# MSP-EXP432P401R.net
KiCad netlist of a schematic drawn in EAGLE
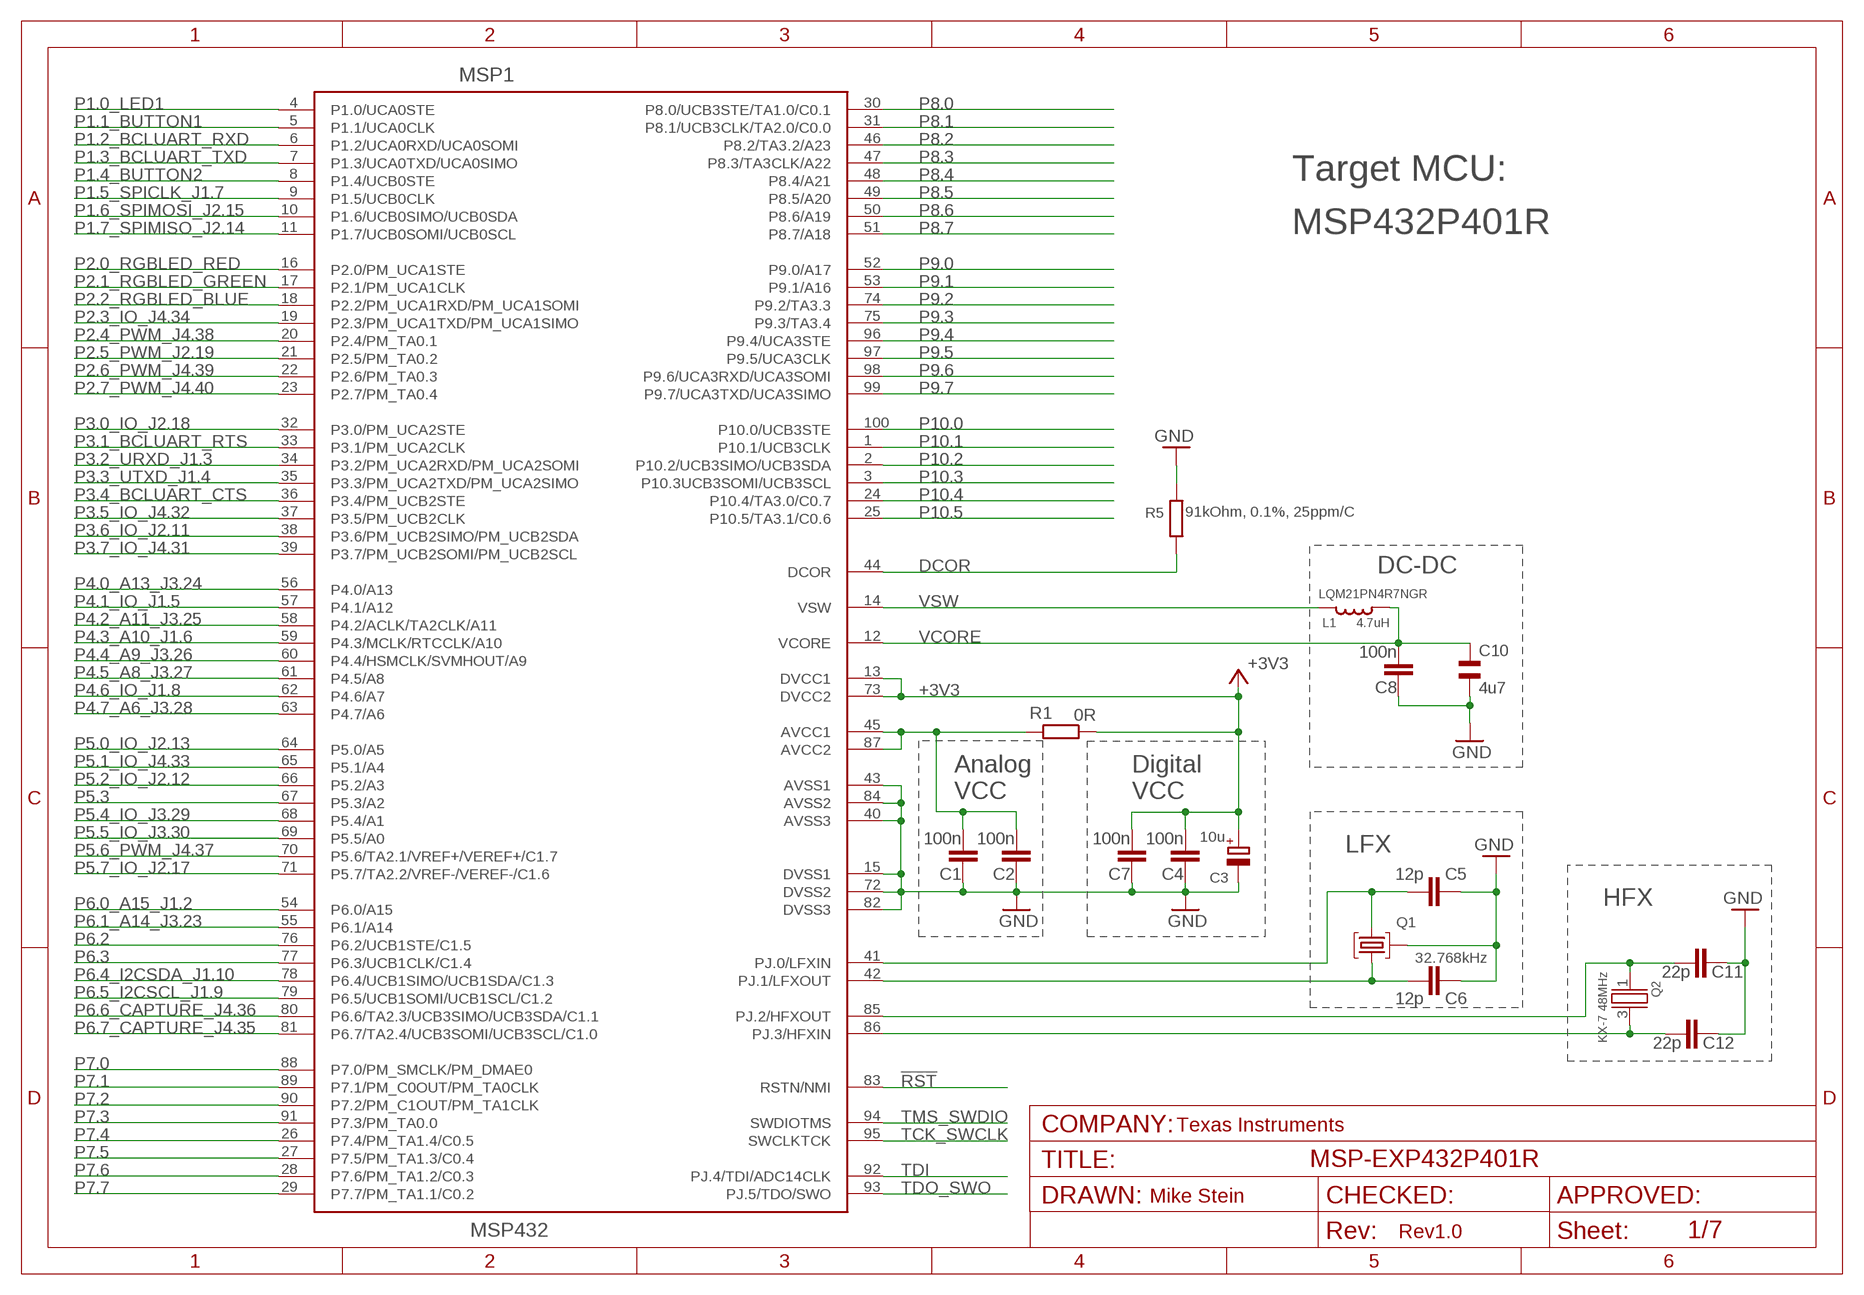
[diagram p0: schematic, sheet 1]
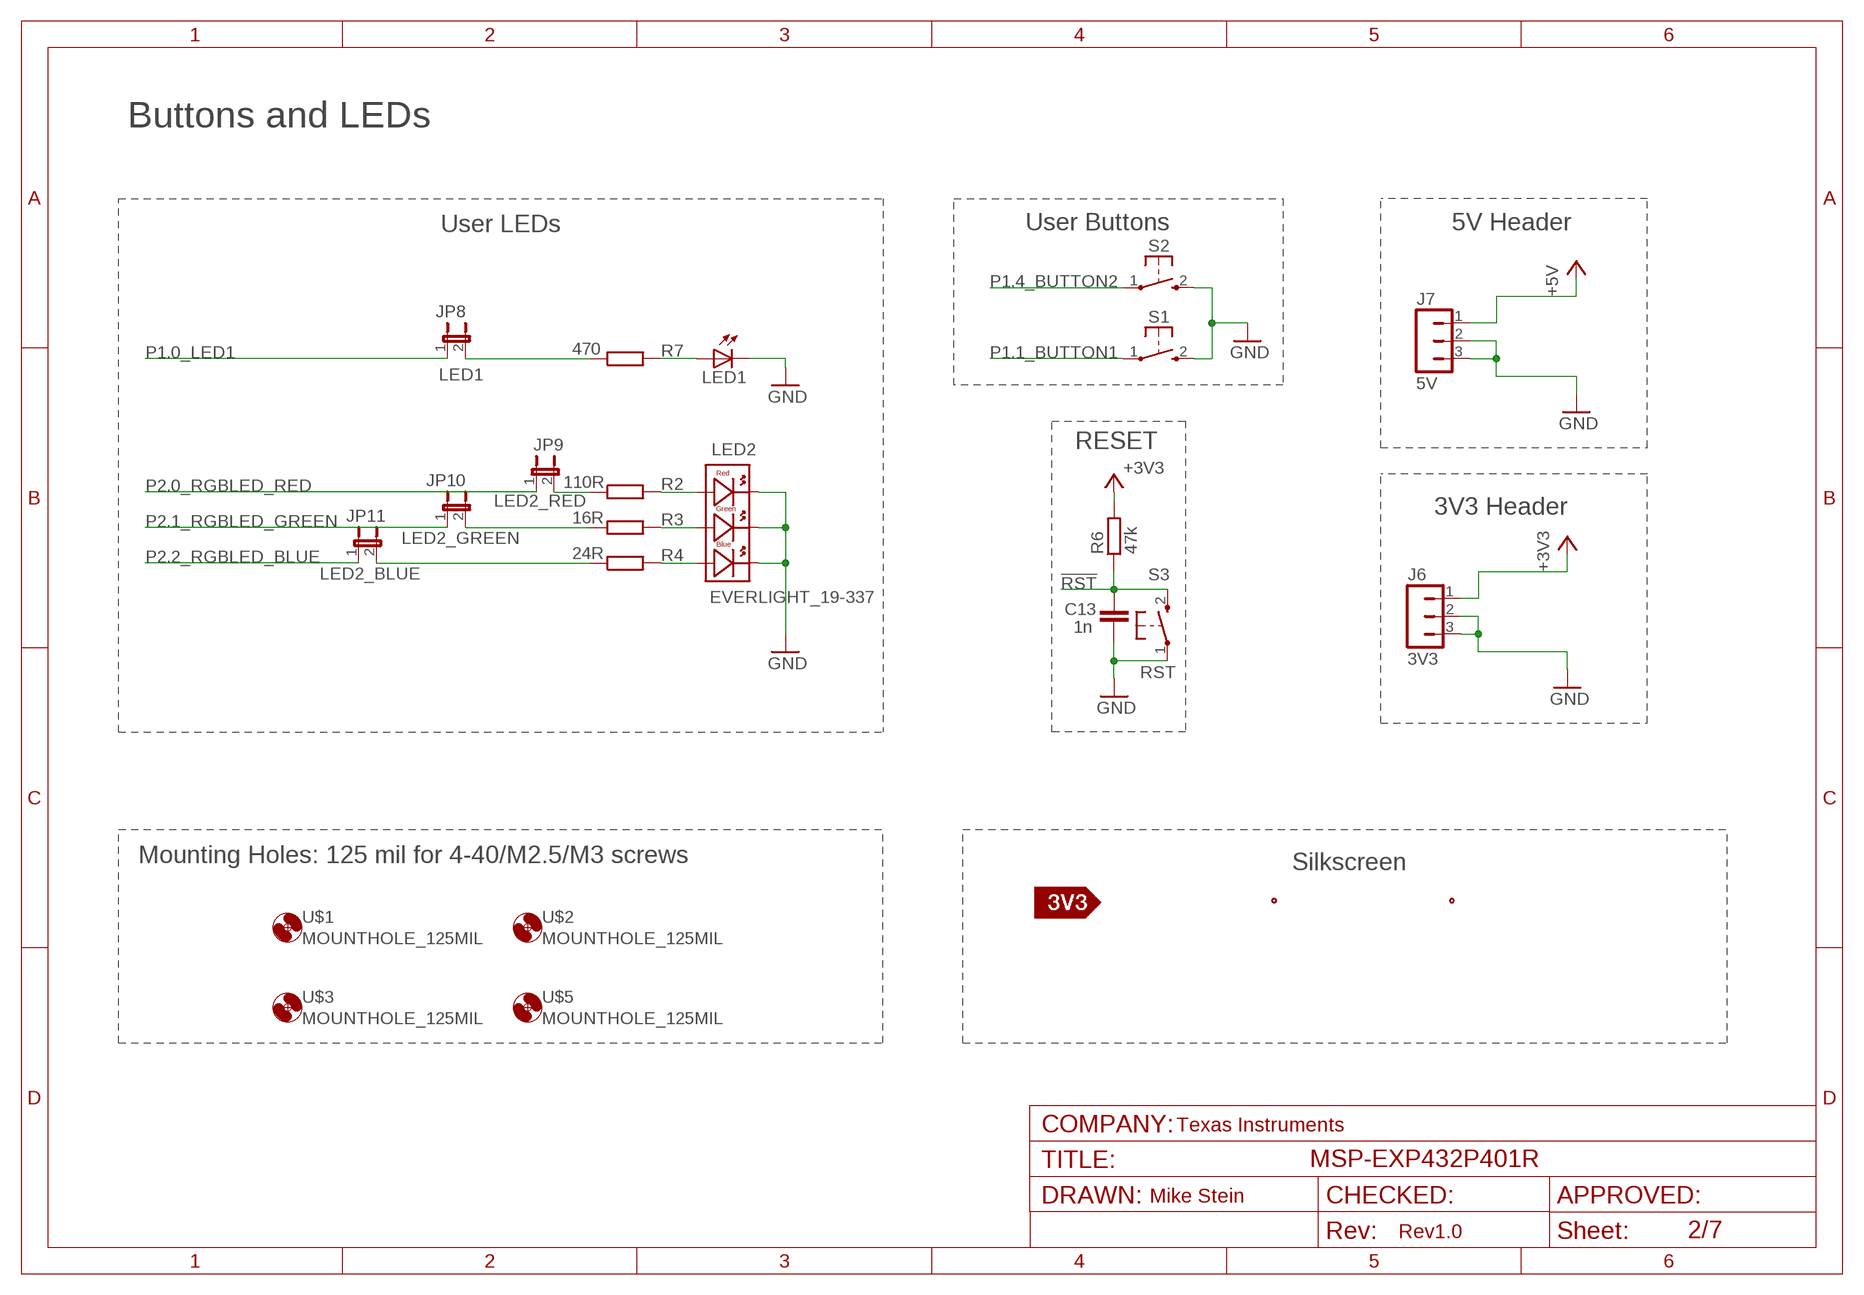
[diagram p1: schematic, sheet 2]
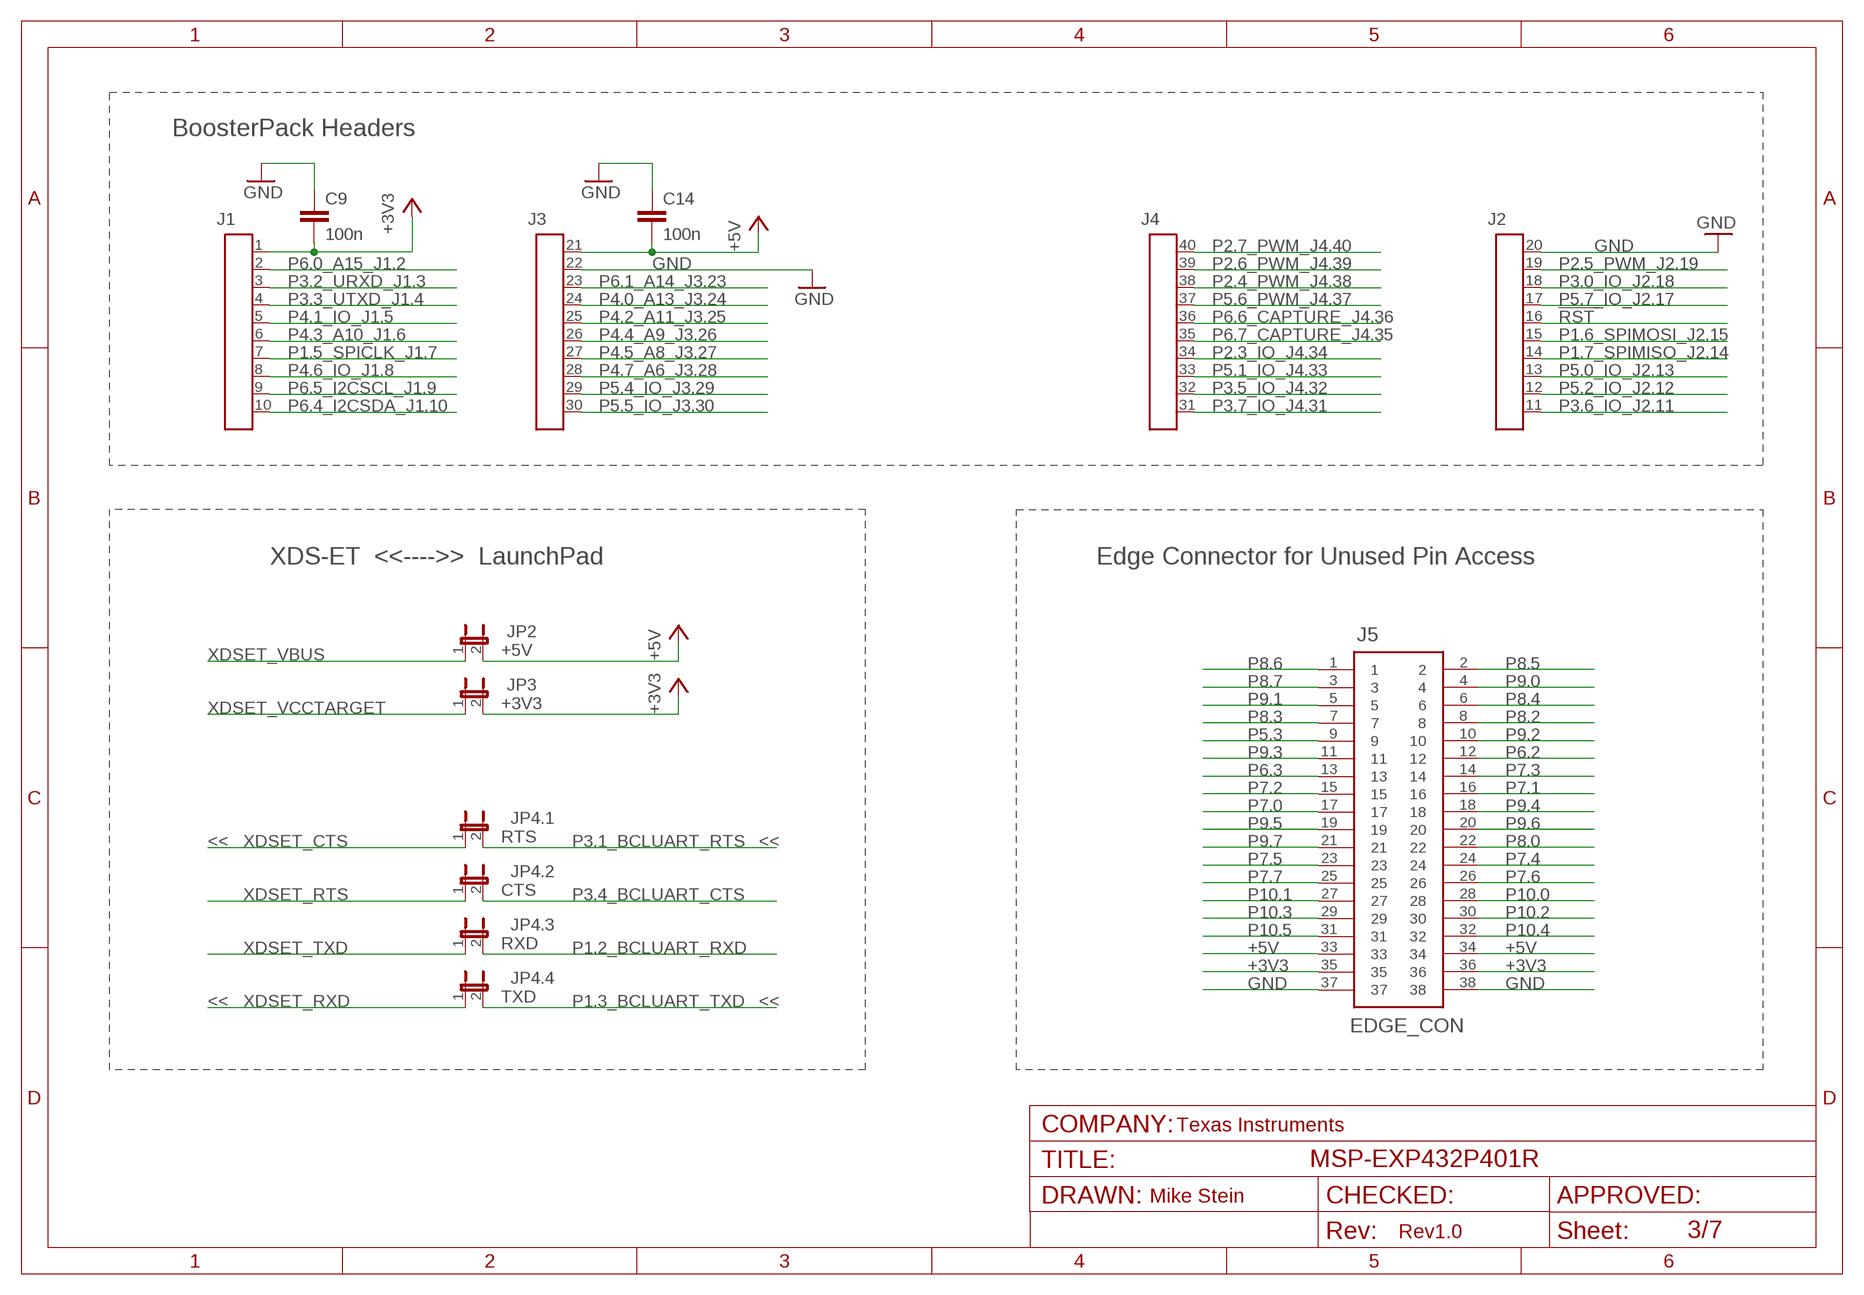
[diagram p2: schematic, sheet 3]
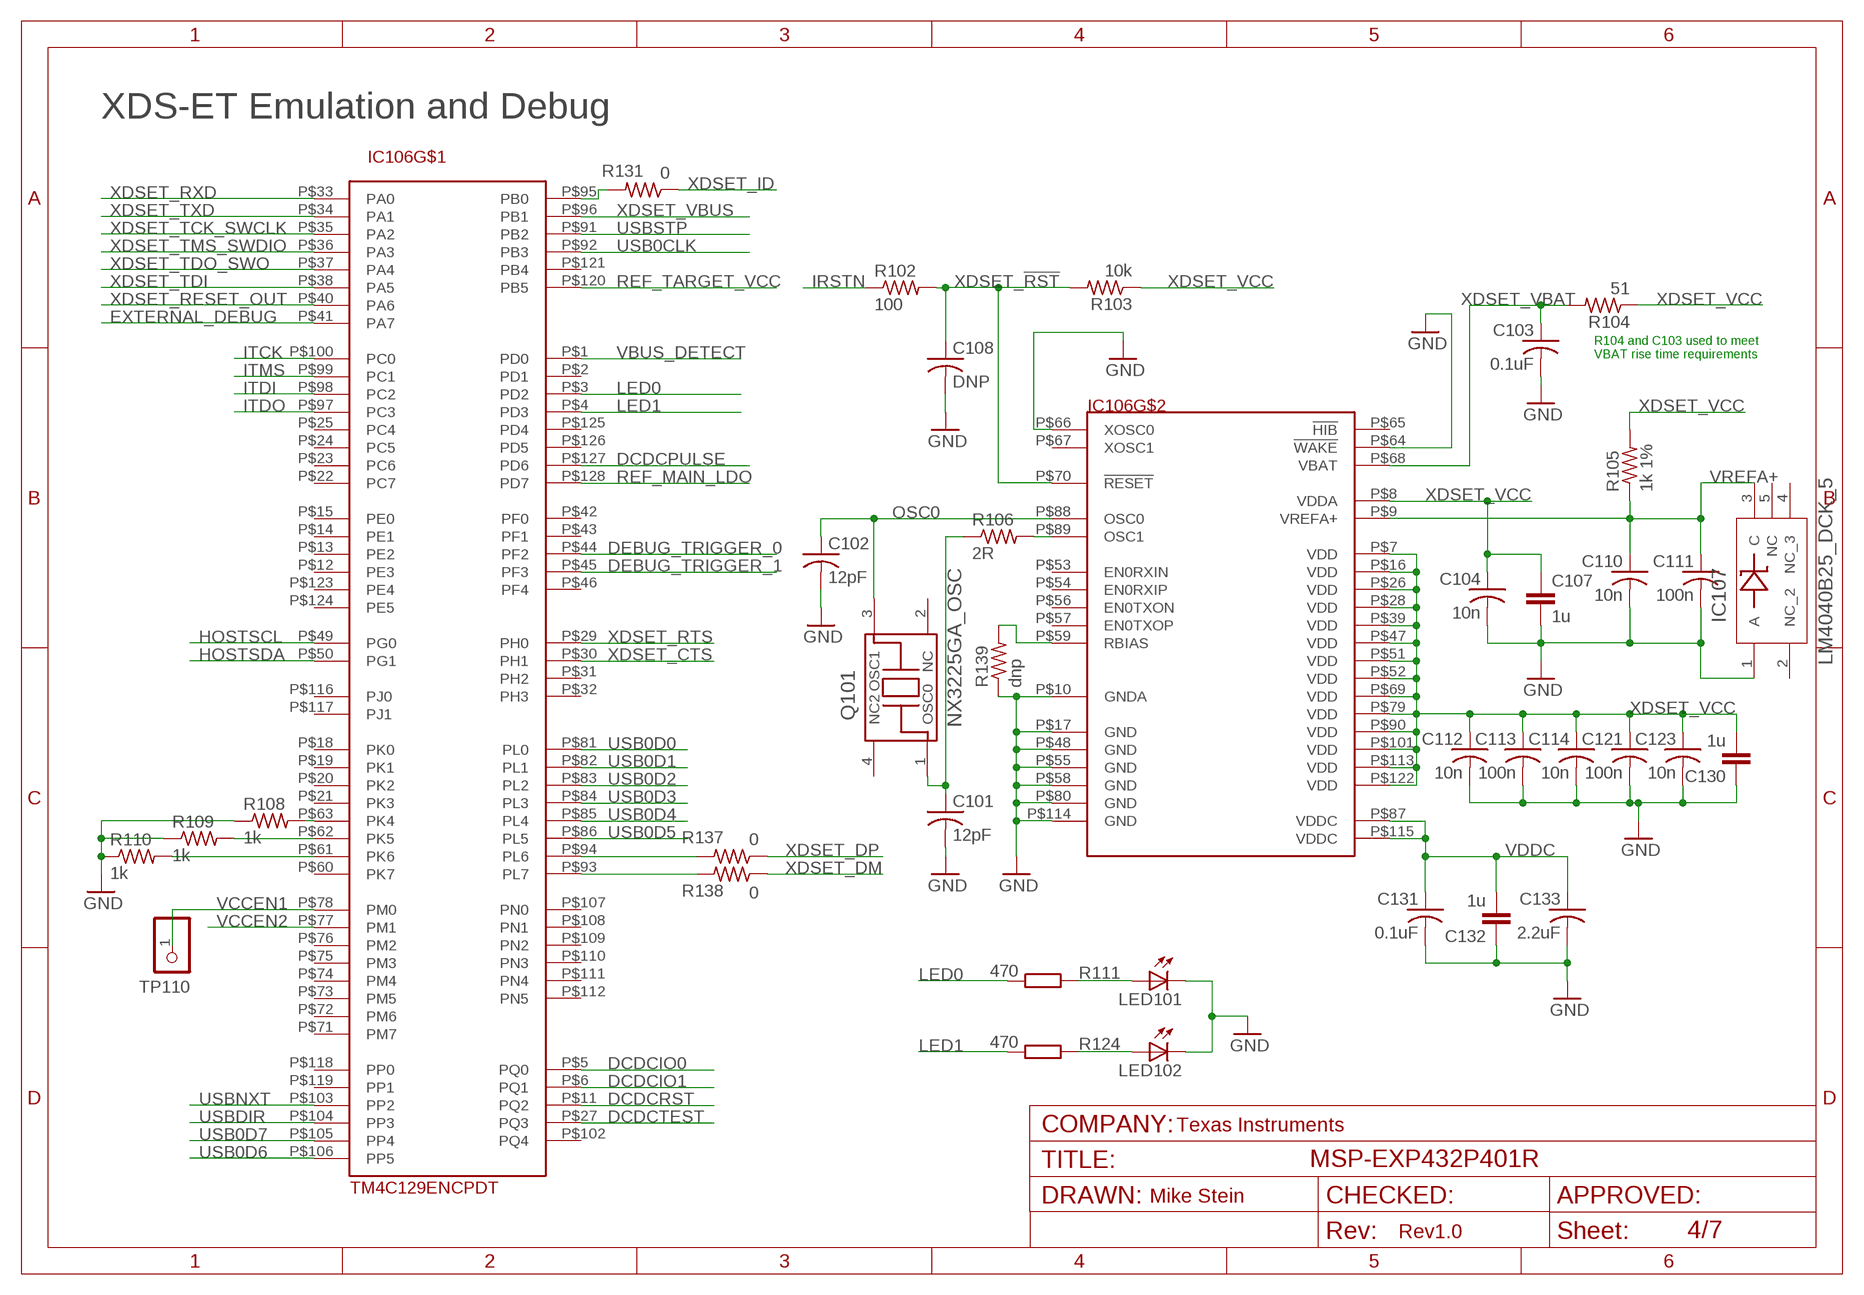
[diagram p3: schematic, sheet 4]
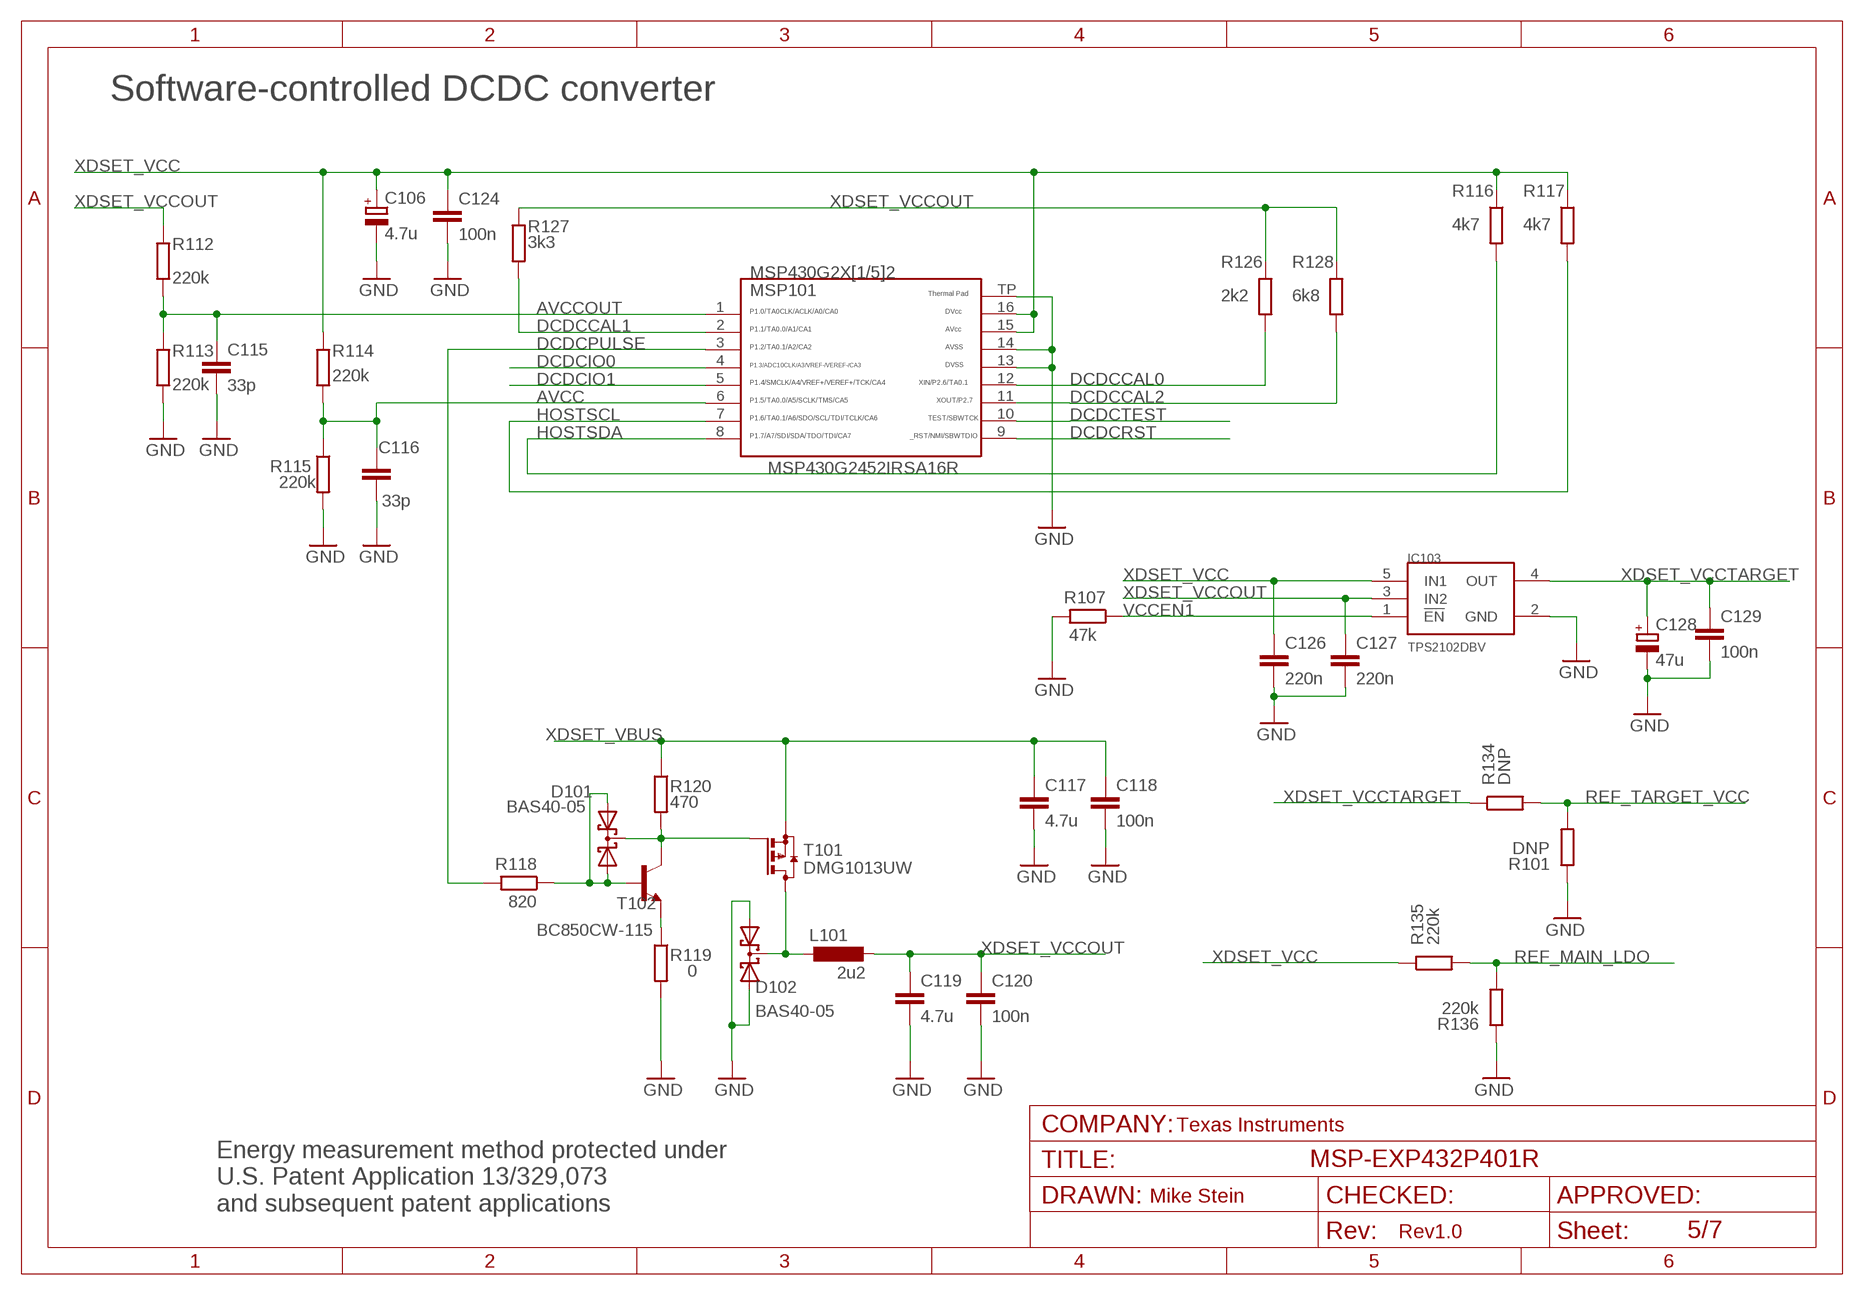
[diagram p4: schematic, sheet 5]
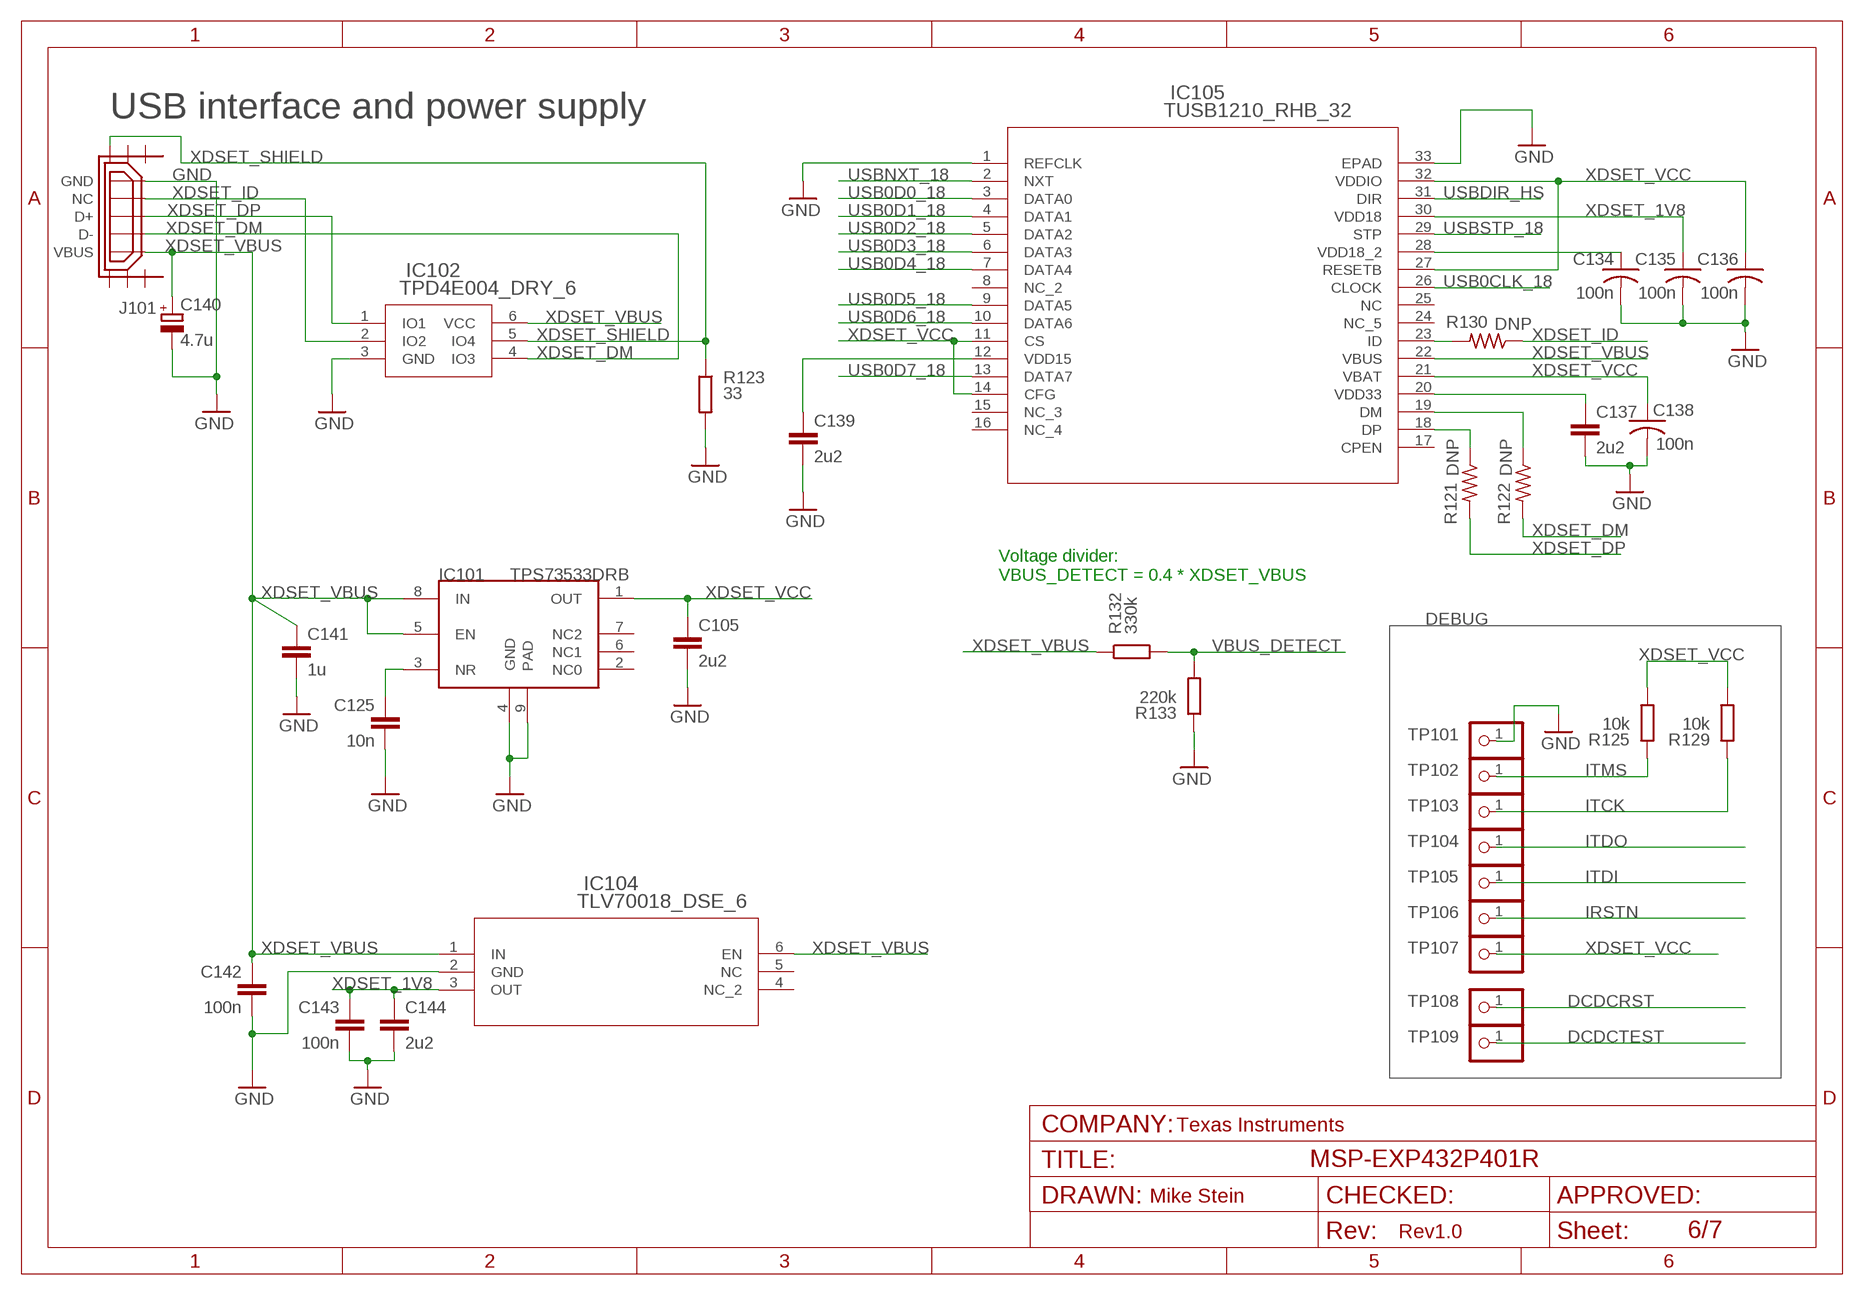
[diagram p5: schematic, sheet 6]
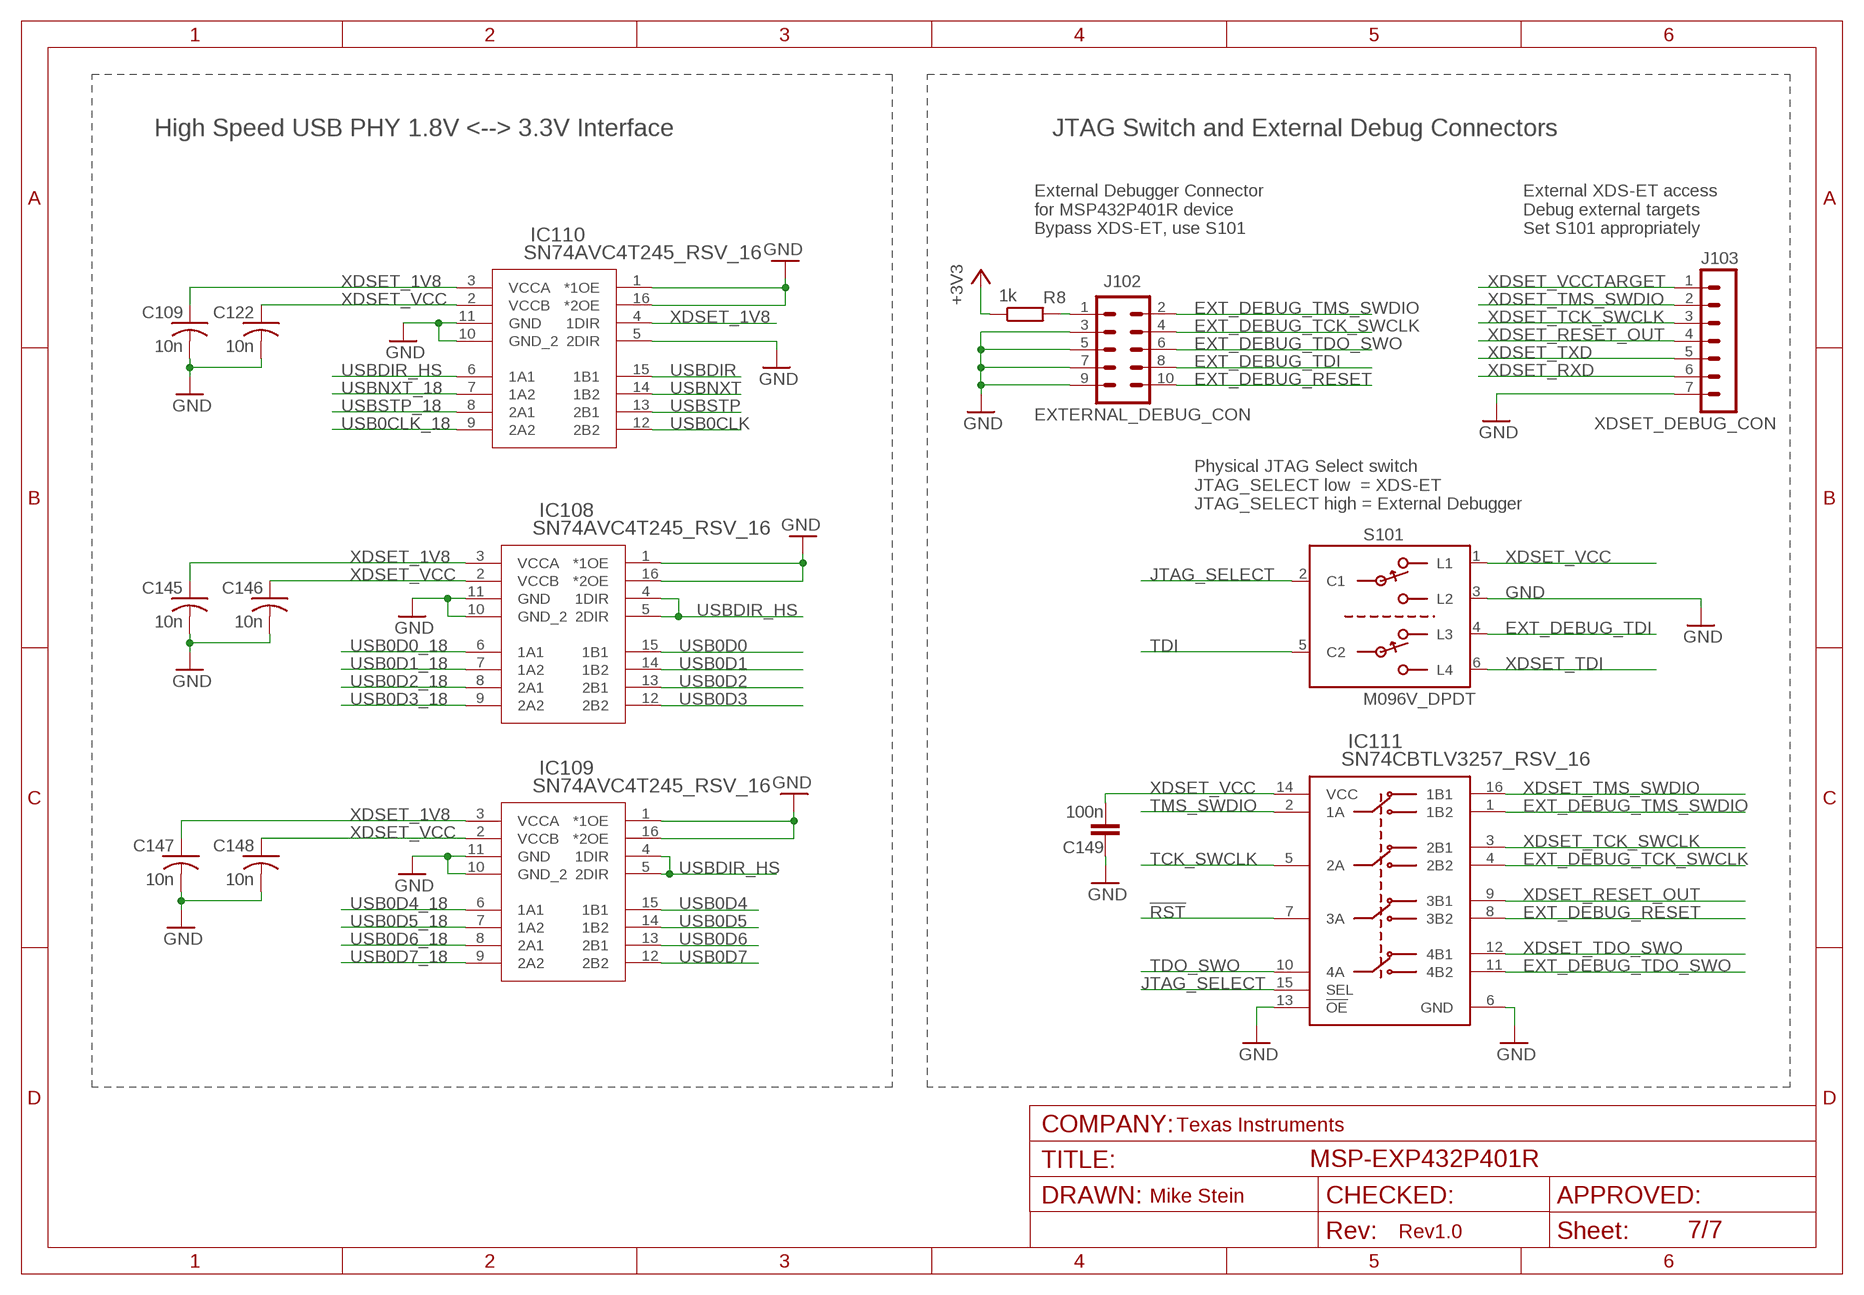
[diagram p6: schematic, sheet 7]

(export (version "E")
  (design (tool "Eeschema 10.0.6"))
  (components
    (comp (ref "C105")
      (value "2u2")
      (footprint "eagle-import:C0603")
      (libsource (lib "eagle-import") (part "C-EUC0603"))
    )
    (comp (ref "C125")
      (value "10n")
      (footprint "eagle-import:0402")
      (libsource (lib "eagle-import") (part "C-EUCM0402"))
    )
    (comp (ref "C134")
      (value "100n")
      (footprint "eagle-import:C0402")
      (libsource (lib "eagle-import") (part "C-USC0402"))
    )
    (comp (ref "C135")
      (value "100n")
      (footprint "eagle-import:C0402")
      (libsource (lib "eagle-import") (part "C-USC0402"))
    )
    (comp (ref "C136")
      (value "100n")
      (footprint "eagle-import:C0402")
      (libsource (lib "eagle-import") (part "C-USC0402"))
    )
    (comp (ref "C137")
      (value "2u2")
      (footprint "eagle-import:C0603")
      (libsource (lib "eagle-import") (part "C-EUC0603"))
    )
    (comp (ref "C138")
      (value "100n")
      (footprint "eagle-import:C0402")
      (libsource (lib "eagle-import") (part "C-USC0402"))
    )
    (comp (ref "C139")
      (value "2u2")
      (footprint "eagle-import:C0603")
      (libsource (lib "eagle-import") (part "C-EUC0603"))
    )
    (comp (ref "C140")
      (value "4.7u")
      (footprint "eagle-import:A_3216-18R")
      (libsource (lib "eagle-import") (part "CPOL-EUA/3216-18R"))
    )
    (comp (ref "C141")
      (value "1u")
      (footprint "eagle-import:C0603")
      (libsource (lib "eagle-import") (part "C-EUC0603"))
    )
    (comp (ref "C142")
      (value "100n")
      (footprint "eagle-import:0402")
      (libsource (lib "eagle-import") (part "C-EUCM0402"))
    )
    (comp (ref "C143")
      (value "100n")
      (footprint "eagle-import:0402")
      (libsource (lib "eagle-import") (part "C-EUCM0402"))
    )
    (comp (ref "C144")
      (value "2u2")
      (footprint "eagle-import:C0603")
      (libsource (lib "eagle-import") (part "C-EUC0603"))
    )
    (comp (ref "IC101")
      (value "TPS73533DRB")
      (footprint "eagle-import:SON8")
      (libsource (lib "eagle-import") (part "TPS73633DRB"))
    )
    (comp (ref "IC102")
      (value "TPD4E004_DRY_6")
      (footprint "eagle-import:DRY6")
      (fields
        (field (name "GENERIC_PART_NUMBER") "TPD4E004")
        (field (name "MANUFACTURER") "Texas Instruments")
        (field (name "MANUFACTURER_PART_NUMBER") "tpd4e004_dry_6")
      )
      (libsource (lib "eagle-import") (part "TPD4E004_DRY_6"))
    )
    (comp (ref "IC104")
      (value "TLV70018_DSE_6")
      (footprint "eagle-import:DSE6")
      (fields
        (field (name "GENERIC_PART_NUMBER") "TLV70018")
        (field (name "MANUFACTURER") "Texas Instruments")
        (field (name "MANUFACTURER_PART_NUMBER") "tlv70018_dse_6")
      )
      (libsource (lib "eagle-import") (part "TLV70018_DSE_6"))
    )
    (comp (ref "IC105")
      (value "TUSB1210_RHB_32")
      (footprint "eagle-import:RHB32_3P45X3P45")
      (fields
        (field (name "GENERIC_PART_NUMBER") "TUSB1210")
        (field (name "MANUFACTURER") "Texas Instruments")
        (field (name "MANUFACTURER_PART_NUMBER") "tusb1210_rhb_32")
      )
      (libsource (lib "eagle-import") (part "TUSB1210_RHB_32"))
    )
    (comp (ref "J101")
      (value "USB_MICRO_FLIPPED")
      (footprint "eagle-import:HIROSE-ZX62R-B-5P")
      (libsource (lib "eagle-import") (part "USB_MICRO_FLIPPED"))
    )
    (comp (ref "R121")
      (value "DNP")
      (footprint "eagle-import:R0402")
      (libsource (lib "eagle-import") (part "R-US_R0402"))
    )
    (comp (ref "R122")
      (value "DNP")
      (footprint "eagle-import:R0402")
      (libsource (lib "eagle-import") (part "R-US_R0402"))
    )
    (comp (ref "R123")
      (value "33")
      (footprint "eagle-import:0402")
      (libsource (lib "eagle-import") (part "R-EU_RM0402"))
    )
    (comp (ref "R125")
      (value "10k")
      (footprint "eagle-import:0402")
      (libsource (lib "eagle-import") (part "R-EU_RM0402"))
    )
    (comp (ref "R129")
      (value "10k")
      (footprint "eagle-import:0402")
      (libsource (lib "eagle-import") (part "R-EU_RM0402"))
    )
    (comp (ref "R130")
      (value "DNP")
      (footprint "eagle-import:R0402")
      (libsource (lib "eagle-import") (part "R-US_R0402"))
    )
    (comp (ref "R132")
      (value "330k")
      (footprint "eagle-import:0402")
      (libsource (lib "eagle-import") (part "R-EU_RM0402"))
    )
    (comp (ref "R133")
      (value "220k")
      (footprint "eagle-import:0402")
      (libsource (lib "eagle-import") (part "R-EU_RM0402"))
    )
    (comp (ref "TP101")
      (value "TEST_PIN2")
      (footprint "eagle-import:1X01")
      (libsource (lib "eagle-import") (part "PINHD-1X1"))
    )
    (comp (ref "TP102")
      (value "TEST_PIN2")
      (footprint "eagle-import:1X01")
      (libsource (lib "eagle-import") (part "PINHD-1X1"))
    )
    (comp (ref "TP103")
      (value "TEST_PIN2")
      (footprint "eagle-import:1X01")
      (libsource (lib "eagle-import") (part "PINHD-1X1"))
    )
    (comp (ref "TP104")
      (value "TEST_PIN2")
      (footprint "eagle-import:1X01")
      (libsource (lib "eagle-import") (part "PINHD-1X1"))
    )
    (comp (ref "TP105")
      (value "TEST_PIN2")
      (footprint "eagle-import:1X01")
      (libsource (lib "eagle-import") (part "PINHD-1X1"))
    )
    (comp (ref "TP106")
      (value "TEST_PIN2")
      (footprint "eagle-import:1X01")
      (libsource (lib "eagle-import") (part "PINHD-1X1"))
    )
    (comp (ref "TP107")
      (value "TEST_PIN2")
      (footprint "eagle-import:1X01")
      (libsource (lib "eagle-import") (part "PINHD-1X1"))
    )
    (comp (ref "TP108")
      (value "TEST_PIN2")
      (footprint "eagle-import:1X01")
      (libsource (lib "eagle-import") (part "PINHD-1X1"))
    )
    (comp (ref "TP109")
      (value "TEST_PIN2")
      (footprint "eagle-import:1X01")
      (libsource (lib "eagle-import") (part "PINHD-1X1"))
    )
    (comp (ref "C109")
      (value "10n")
      (footprint "eagle-import:C0402")
      (libsource (lib "eagle-import") (part "C-USC0402"))
    )
    (comp (ref "C122")
      (value "10n")
      (footprint "eagle-import:C0402")
      (libsource (lib "eagle-import") (part "C-USC0402"))
    )
    (comp (ref "C145")
      (value "10n")
      (footprint "eagle-import:C0402")
      (libsource (lib "eagle-import") (part "C-USC0402"))
    )
    (comp (ref "C146")
      (value "10n")
      (footprint "eagle-import:C0402")
      (libsource (lib "eagle-import") (part "C-USC0402"))
    )
    (comp (ref "C147")
      (value "10n")
      (footprint "eagle-import:C0402")
      (libsource (lib "eagle-import") (part "C-USC0402"))
    )
    (comp (ref "C148")
      (value "10n")
      (footprint "eagle-import:C0402")
      (libsource (lib "eagle-import") (part "C-USC0402"))
    )
    (comp (ref "C149")
      (value "100n")
      (footprint "eagle-import:0402")
      (libsource (lib "eagle-import") (part "C-EUCM0402"))
    )
    (comp (ref "IC108")
      (value "SN74AVC4T245_RSV_16")
      (footprint "eagle-import:RSV16")
      (fields
        (field (name "GENERIC_PART_NUMBER") "SN74AVC4T245")
        (field (name "MANUFACTURER") "Texas Instruments")
        (field (name "MANUFACTURER_PART_NUMBER") "sn74avc4t245_rsv_16")
      )
      (libsource (lib "eagle-import") (part "SN74AVC4T245_RSV_16"))
    )
    (comp (ref "IC109")
      (value "SN74AVC4T245_RSV_16")
      (footprint "eagle-import:RSV16")
      (fields
        (field (name "GENERIC_PART_NUMBER") "SN74AVC4T245")
        (field (name "MANUFACTURER") "Texas Instruments")
        (field (name "MANUFACTURER_PART_NUMBER") "sn74avc4t245_rsv_16")
      )
      (libsource (lib "eagle-import") (part "SN74AVC4T245_RSV_16"))
    )
    (comp (ref "IC110")
      (value "SN74AVC4T245_RSV_16")
      (footprint "eagle-import:RSV16")
      (fields
        (field (name "GENERIC_PART_NUMBER") "SN74AVC4T245")
        (field (name "MANUFACTURER") "Texas Instruments")
        (field (name "MANUFACTURER_PART_NUMBER") "sn74avc4t245_rsv_16")
      )
      (libsource (lib "eagle-import") (part "SN74AVC4T245_RSV_16"))
    )
    (comp (ref "IC111")
      (value "SN74CBTLV3257_RSV_16")
      (footprint "eagle-import:RSV16")
      (libsource (lib "eagle-import") (part "SN74CBTLV3257_RSV_16"))
    )
    (comp (ref "J102")
      (value "EXTERNAL_DEBUG_CON")
      (footprint "eagle-import:EXTERNAL_DEBUG")
      (libsource (lib "eagle-import") (part "EXTERNAL_DEBUG_CON"))
    )
    (comp (ref "J103")
      (value "XDSET_DEBUG_CON")
      (footprint "eagle-import:XDSET_DEBUG")
      (libsource (lib "eagle-import") (part "XDSET_DEBUG_CON"))
    )
    (comp (ref "R8")
      (value "1k")
      (footprint "eagle-import:0402")
      (libsource (lib "eagle-import") (part "R-EU_RM0402"))
    )
    (comp (ref "S101")
      (value "M096V_DPDT")
      (footprint "eagle-import:M096V_DPDT")
      (libsource (lib "eagle-import") (part "M096V_DPDT"))
    )
    (comp (ref "C101")
      (value "12pF")
      (footprint "eagle-import:C0402")
      (libsource (lib "eagle-import") (part "C-USC0402"))
    )
    (comp (ref "C102")
      (value "12pF")
      (footprint "eagle-import:C0402")
      (libsource (lib "eagle-import") (part "C-USC0402"))
    )
    (comp (ref "C103")
      (value "0.1uF")
      (footprint "eagle-import:C0402")
      (libsource (lib "eagle-import") (part "C-USC0402"))
    )
    (comp (ref "C104")
      (value "10n")
      (footprint "eagle-import:C0402")
      (libsource (lib "eagle-import") (part "C-USC0402"))
    )
    (comp (ref "C107")
      (value "1u")
      (footprint "eagle-import:C0603")
      (libsource (lib "eagle-import") (part "C-EUC0603"))
    )
    (comp (ref "C108")
      (value "DNP")
      (footprint "eagle-import:C0402")
      (libsource (lib "eagle-import") (part "C-USC0402"))
    )
    (comp (ref "C110")
      (value "10n")
      (footprint "eagle-import:C0402")
      (libsource (lib "eagle-import") (part "C-USC0402"))
    )
    (comp (ref "C111")
      (value "100n")
      (footprint "eagle-import:C0402")
      (libsource (lib "eagle-import") (part "C-USC0402"))
    )
    (comp (ref "C112")
      (value "10n")
      (footprint "eagle-import:C0402")
      (libsource (lib "eagle-import") (part "C-USC0402"))
    )
    (comp (ref "C113")
      (value "100n")
      (footprint "eagle-import:C0402")
      (libsource (lib "eagle-import") (part "C-USC0402"))
    )
    (comp (ref "C114")
      (value "10n")
      (footprint "eagle-import:C0402")
      (libsource (lib "eagle-import") (part "C-USC0402"))
    )
    (comp (ref "C121")
      (value "100n")
      (footprint "eagle-import:C0402")
      (libsource (lib "eagle-import") (part "C-USC0402"))
    )
    (comp (ref "C123")
      (value "10n")
      (footprint "eagle-import:C0402")
      (libsource (lib "eagle-import") (part "C-USC0402"))
    )
    (comp (ref "C130")
      (value "1u")
      (footprint "eagle-import:C0603")
      (libsource (lib "eagle-import") (part "C-EUC0603"))
    )
    (comp (ref "C131")
      (value "0.1uF")
      (footprint "eagle-import:C0402")
      (libsource (lib "eagle-import") (part "C-USC0402"))
    )
    (comp (ref "C132")
      (value "1u")
      (footprint "eagle-import:C0603")
      (libsource (lib "eagle-import") (part "C-EUC0603"))
    )
    (comp (ref "C133")
      (value "2.2uF")
      (footprint "eagle-import:C0603K")
      (fields (field (name "DIGIKEY_PARTNUM") "311-1451-2-ND"))
      (libsource (lib "eagle-import") (part "C-USC0603K"))
    )
    (comp (ref "IC106")
      (value "TM4C129ENCPDT")
      (footprint "eagle-import:TQFP-128")
      (libsource (lib "eagle-import") (part "TM4C129ENCPDT"))
    )
    (comp (ref "IC107")
      (value "LM4040B25_DCK_5")
      (footprint "eagle-import:DCK5")
      (fields
        (field (name "GENERIC_PART_NUMBER") "LM4040B25")
        (field (name "MANUFACTURER") "Texas Instruments")
        (field (name "MANUFACTURER_PART_NUMBER") "lm4040b25_dck_5")
      )
      (libsource (lib "eagle-import") (part "LM4040B25_DCK_5"))
    )
    (comp (ref "LED101")
      (value "LEDCHIPLED_0603")
      (footprint "eagle-import:CHIPLED_0603")
      (libsource (lib "eagle-import") (part "LEDCHIPLED_0603"))
    )
    (comp (ref "LED102")
      (value "LEDCHIPLED_0603")
      (footprint "eagle-import:CHIPLED_0603")
      (libsource (lib "eagle-import") (part "LEDCHIPLED_0603"))
    )
    (comp (ref "Q101")
      (value "NX3225GA_OSC")
      (footprint "eagle-import:NX3225GA")
      (libsource (lib "eagle-import") (part "NX3225GA_OSC"))
    )
    (comp (ref "R102")
      (value "100")
      (footprint "eagle-import:R0402")
      (libsource (lib "eagle-import") (part "R-US_R0402"))
    )
    (comp (ref "R103")
      (value "10k")
      (footprint "eagle-import:R0402")
      (libsource (lib "eagle-import") (part "R-US_R0402"))
    )
    (comp (ref "R104")
      (value "51")
      (footprint "eagle-import:R0402")
      (libsource (lib "eagle-import") (part "R-US_R0402"))
    )
    (comp (ref "R105")
      (value "1k 1%")
      (footprint "eagle-import:R0402")
      (libsource (lib "eagle-import") (part "R-US_R0402"))
    )
    (comp (ref "R106")
      (value "2R")
      (footprint "eagle-import:R0402")
      (libsource (lib "eagle-import") (part "R-US_R0402"))
    )
    (comp (ref "R108")
      (value "1k")
      (footprint "eagle-import:R0402")
      (libsource (lib "eagle-import") (part "R-US_R0402"))
    )
    (comp (ref "R109")
      (value "1k")
      (footprint "eagle-import:R0402")
      (libsource (lib "eagle-import") (part "R-US_R0402"))
    )
    (comp (ref "R110")
      (value "1k")
      (footprint "eagle-import:R0402")
      (libsource (lib "eagle-import") (part "R-US_R0402"))
    )
    (comp (ref "R111")
      (value "470")
      (footprint "eagle-import:0402")
      (libsource (lib "eagle-import") (part "R-EU_RM0402"))
    )
    (comp (ref "R124")
      (value "470")
      (footprint "eagle-import:0402")
      (libsource (lib "eagle-import") (part "R-EU_RM0402"))
    )
    (comp (ref "R131")
      (value "0")
      (footprint "eagle-import:R0402")
      (libsource (lib "eagle-import") (part "R-US_R0402"))
    )
    (comp (ref "R137")
      (value "0")
      (footprint "eagle-import:R0402")
      (libsource (lib "eagle-import") (part "R-US_R0402"))
    )
    (comp (ref "R138")
      (value "0")
      (footprint "eagle-import:R0402")
      (libsource (lib "eagle-import") (part "R-US_R0402"))
    )
    (comp (ref "R139")
      (value "dnp")
      (footprint "eagle-import:R0402")
      (libsource (lib "eagle-import") (part "R-US_R0402"))
    )
    (comp (ref "TP110")
      (value "TEST_PIN2")
      (footprint "eagle-import:1X01")
      (libsource (lib "eagle-import") (part "PINHD-1X1"))
    )
    (comp (ref "C106")
      (value "4.7u")
      (footprint "eagle-import:A_3216-18R")
      (libsource (lib "eagle-import") (part "CPOL-EUA/3216-18R"))
    )
    (comp (ref "C115")
      (value "33p")
      (footprint "eagle-import:0402")
      (libsource (lib "eagle-import") (part "C-EUCM0402"))
    )
    (comp (ref "C116")
      (value "33p")
      (footprint "eagle-import:0402")
      (libsource (lib "eagle-import") (part "C-EUCM0402"))
    )
    (comp (ref "C117")
      (value "4.7u")
      (footprint "eagle-import:C0603")
      (libsource (lib "eagle-import") (part "C-EUC0603"))
    )
    (comp (ref "C118")
      (value "100n")
      (footprint "eagle-import:0402")
      (libsource (lib "eagle-import") (part "C-EUCM0402"))
    )
    (comp (ref "C119")
      (value "4.7u")
      (footprint "eagle-import:C0603")
      (libsource (lib "eagle-import") (part "C-EUC0603"))
    )
    (comp (ref "C120")
      (value "100n")
      (footprint "eagle-import:0402")
      (libsource (lib "eagle-import") (part "C-EUCM0402"))
    )
    (comp (ref "C124")
      (value "100n")
      (footprint "eagle-import:0402")
      (libsource (lib "eagle-import") (part "C-EUCM0402"))
    )
    (comp (ref "C126")
      (value "220n")
      (footprint "eagle-import:0402")
      (libsource (lib "eagle-import") (part "C-EUCM0402"))
    )
    (comp (ref "C127")
      (value "220n")
      (footprint "eagle-import:0402")
      (libsource (lib "eagle-import") (part "C-EUCM0402"))
    )
    (comp (ref "C128")
      (value "47u")
      (footprint "eagle-import:A_3216-18R")
      (libsource (lib "eagle-import") (part "CPOL-EUA/3216-18R"))
    )
    (comp (ref "C129")
      (value "100n")
      (footprint "eagle-import:0402")
      (libsource (lib "eagle-import") (part "C-EUCM0402"))
    )
    (comp (ref "D101")
      (value "BAS40-05")
      (footprint "eagle-import:SOT23")
      (libsource (lib "eagle-import") (part "BAS70-05"))
    )
    (comp (ref "D102")
      (value "BAS40-05")
      (footprint "eagle-import:SOT23")
      (libsource (lib "eagle-import") (part "BAS70-05"))
    )
    (comp (ref "IC103")
      (value "TPS2102DBV")
      (footprint "eagle-import:SOT23-5")
      (libsource (lib "eagle-import") (part "TPS2102DBV"))
    )
    (comp (ref "L101")
      (value "2u2")
      (footprint "eagle-import:L3216C")
      (libsource (lib "eagle-import") (part "L-EUL3216C"))
    )
    (comp (ref "MSP101")
      (value "MSP430G2452IRSA16R")
      (footprint "eagle-import:RSA16")
      (libsource (lib "eagle-import") (part "G2X[1/5]2---RSA16"))
    )
    (comp (ref "R101")
      (value "DNP")
      (footprint "eagle-import:0402")
      (libsource (lib "eagle-import") (part "R-EU_RM0402"))
    )
    (comp (ref "R107")
      (value "47k")
      (footprint "eagle-import:0402")
      (libsource (lib "eagle-import") (part "R-EU_RM0402"))
    )
    (comp (ref "R112")
      (value "220k")
      (footprint "eagle-import:0402")
      (libsource (lib "eagle-import") (part "R-EU_RM0402"))
    )
    (comp (ref "R113")
      (value "220k")
      (footprint "eagle-import:0402")
      (libsource (lib "eagle-import") (part "R-EU_RM0402"))
    )
    (comp (ref "R114")
      (value "220k")
      (footprint "eagle-import:0402")
      (libsource (lib "eagle-import") (part "R-EU_RM0402"))
    )
    (comp (ref "R115")
      (value "220k")
      (footprint "eagle-import:0402")
      (libsource (lib "eagle-import") (part "R-EU_RM0402"))
    )
    (comp (ref "R116")
      (value "4k7")
      (footprint "eagle-import:0402")
      (libsource (lib "eagle-import") (part "R-EU_RM0402"))
    )
    (comp (ref "R117")
      (value "4k7")
      (footprint "eagle-import:0402")
      (libsource (lib "eagle-import") (part "R-EU_RM0402"))
    )
    (comp (ref "R118")
      (value "820")
      (footprint "eagle-import:0402")
      (libsource (lib "eagle-import") (part "R-EU_RM0402"))
    )
    (comp (ref "R119")
      (value "0")
      (footprint "eagle-import:0402")
      (libsource (lib "eagle-import") (part "R-EU_RM0402"))
    )
    (comp (ref "R120")
      (value "470")
      (footprint "eagle-import:0402")
      (libsource (lib "eagle-import") (part "R-EU_RM0402"))
    )
    (comp (ref "R126")
      (value "2k2")
      (footprint "eagle-import:0402")
      (libsource (lib "eagle-import") (part "R-EU_RM0402"))
    )
    (comp (ref "R127")
      (value "3k3")
      (footprint "eagle-import:0402")
      (libsource (lib "eagle-import") (part "R-EU_RM0402"))
    )
    (comp (ref "R128")
      (value "6k8")
      (footprint "eagle-import:0402")
      (libsource (lib "eagle-import") (part "R-EU_RM0402"))
    )
    (comp (ref "R134")
      (value "DNP")
      (footprint "eagle-import:0402")
      (libsource (lib "eagle-import") (part "R-EU_RM0402"))
    )
    (comp (ref "R135")
      (value "220k")
      (footprint "eagle-import:0402")
      (libsource (lib "eagle-import") (part "R-EU_RM0402"))
    )
    (comp (ref "R136")
      (value "220k")
      (footprint "eagle-import:0402")
      (libsource (lib "eagle-import") (part "R-EU_RM0402"))
    )
    (comp (ref "T101")
      (value "DMG1013UW")
      (footprint "eagle-import:SOT23")
      (libsource (lib "eagle-import") (part "BSS84"))
    )
    (comp (ref "T102")
      (value "BC850CW-115")
      (footprint "eagle-import:SOT23-BEC")
      (libsource (lib "eagle-import") (part "BC850SMD"))
    )
    (comp (ref "C9")
      (value "100n")
      (footprint "eagle-import:0402")
      (libsource (lib "eagle-import") (part "C-EUCM0402"))
    )
    (comp (ref "C14")
      (value "100n")
      (footprint "eagle-import:0402")
      (libsource (lib "eagle-import") (part "C-EUCM0402"))
    )
    (comp (ref "J1")
      (value "HEADER1X10")
      (footprint "eagle-import:1X10")
      (libsource (lib "eagle-import") (part "HEADER1X10"))
    )
    (comp (ref "J2")
      (value "HEADER1X10-J2")
      (footprint "eagle-import:1X10-J2")
      (libsource (lib "eagle-import") (part "HEADER1X10-J2"))
    )
    (comp (ref "J3")
      (value "HEADER1X10-J3")
      (footprint "eagle-import:1X10-J3")
      (libsource (lib "eagle-import") (part "HEADER1X10-J3"))
    )
    (comp (ref "J4")
      (value "HEADER1X10-J4")
      (footprint "eagle-import:1X10-J4")
      (libsource (lib "eagle-import") (part "HEADER1X10-J4"))
    )
    (comp (ref "J5")
      (value "EDGE_CON")
      (footprint "eagle-import:BOTTOM_CONNECTOR")
      (libsource (lib "eagle-import") (part "EDGE_CON"))
    )
    (comp (ref "JP2")
      (value "+5V")
      (footprint "eagle-import:JP1M")
      (libsource (lib "eagle-import") (part "JP1M"))
    )
    (comp (ref "JP3")
      (value "+3V3")
      (footprint "eagle-import:JP1M")
      (libsource (lib "eagle-import") (part "JP1M"))
    )
    (comp (ref "JP4.1")
      (value "RTS")
      (footprint "eagle-import:JP1M")
      (libsource (lib "eagle-import") (part "JP1M"))
    )
    (comp (ref "JP4.2")
      (value "CTS")
      (footprint "eagle-import:JP1M")
      (libsource (lib "eagle-import") (part "JP1M"))
    )
    (comp (ref "JP4.3")
      (value "RXD")
      (footprint "eagle-import:JP1M")
      (libsource (lib "eagle-import") (part "JP1M"))
    )
    (comp (ref "JP4.4")
      (value "TXD")
      (footprint "eagle-import:JP1M")
      (libsource (lib "eagle-import") (part "JP1M"))
    )
    (comp (ref "C1")
      (value "100n")
      (footprint "eagle-import:0402")
      (libsource (lib "eagle-import") (part "C-EUCM0402"))
    )
    (comp (ref "C2")
      (value "100n")
      (footprint "eagle-import:0402")
      (libsource (lib "eagle-import") (part "C-EUCM0402"))
    )
    (comp (ref "C3")
      (value "10u")
      (footprint "eagle-import:A_3216-18R")
      (libsource (lib "eagle-import") (part "CPOL-EUA/3216-18R"))
    )
    (comp (ref "C4")
      (value "100n")
      (footprint "eagle-import:0402")
      (libsource (lib "eagle-import") (part "C-EUCM0402"))
    )
    (comp (ref "C5")
      (value "12p")
      (footprint "eagle-import:0402")
      (libsource (lib "eagle-import") (part "C-EUCM0402"))
    )
    (comp (ref "C6")
      (value "12p")
      (footprint "eagle-import:0402")
      (libsource (lib "eagle-import") (part "C-EUCM0402"))
    )
    (comp (ref "C7")
      (value "100n")
      (footprint "eagle-import:0402")
      (libsource (lib "eagle-import") (part "C-EUCM0402"))
    )
    (comp (ref "C8")
      (value "100n")
      (footprint "eagle-import:0402")
      (libsource (lib "eagle-import") (part "C-EUCM0402"))
    )
    (comp (ref "C10")
      (value "4u7")
      (footprint "eagle-import:CSMD0805")
      (libsource (lib "eagle-import") (part "CSMD0805"))
    )
    (comp (ref "C11")
      (value "22p")
      (footprint "eagle-import:0402")
      (libsource (lib "eagle-import") (part "C-EUCM0402"))
    )
    (comp (ref "C12")
      (value "22p")
      (footprint "eagle-import:0402")
      (libsource (lib "eagle-import") (part "C-EUCM0402"))
    )
    (comp (ref "L1")
      (value "4.7uH")
      (footprint "eagle-import:0806")
      (libsource (lib "eagle-import") (part "LQM2MP_G0"))
    )
    (comp (ref "MSP1")
      (value "MSP432")
      (footprint "eagle-import:PZ100")
      (libsource (lib "eagle-import") (part "MSP432"))
    )
    (comp (ref "Q1")
      (value "32.768kHz")
      (footprint "eagle-import:MS3V-T1R")
      (libsource (lib "eagle-import") (part "MS3V-T1R"))
    )
    (comp (ref "Q2")
      (value "KX-7 48MHz")
      (footprint "eagle-import:KX-7")
      (libsource (lib "eagle-import") (part "KX-7"))
    )
    (comp (ref "R1")
      (value "0R")
      (footprint "eagle-import:0402")
      (libsource (lib "eagle-import") (part "R-EU_RM0402"))
    )
    (comp (ref "R5")
      (value "91kOhm, 0.1%, 25ppm/C")
      (footprint "eagle-import:0805")
      (libsource (lib "eagle-import") (part "R_0805"))
    )
    (comp (ref "C13")
      (value "1n")
      (footprint "eagle-import:0402")
      (libsource (lib "eagle-import") (part "C-EUCM0402"))
    )
    (comp (ref "J6")
      (value "3V3")
      (footprint "eagle-import:JP3")
      (libsource (lib "eagle-import") (part "JP3"))
    )
    (comp (ref "J7")
      (value "5V")
      (footprint "eagle-import:JP3")
      (libsource (lib "eagle-import") (part "JP3"))
    )
    (comp (ref "JP8")
      (value "LED1")
      (footprint "eagle-import:JP1M")
      (libsource (lib "eagle-import") (part "JP1M"))
    )
    (comp (ref "JP9")
      (value "LED2_RED")
      (footprint "eagle-import:JP1M")
      (libsource (lib "eagle-import") (part "JP1M"))
    )
    (comp (ref "JP10")
      (value "LED2_GREEN")
      (footprint "eagle-import:JP1M")
      (libsource (lib "eagle-import") (part "JP1M"))
    )
    (comp (ref "JP11")
      (value "LED2_BLUE")
      (footprint "eagle-import:JP1M")
      (libsource (lib "eagle-import") (part "JP1M"))
    )
    (comp (ref "LED1")
      (value "LEDCHIPLED_0603")
      (footprint "eagle-import:CHIPLED_0603")
      (libsource (lib "eagle-import") (part "LEDCHIPLED_0603"))
    )
    (comp (ref "LED2")
      (value "EVERLIGHT_19-337")
      (footprint "eagle-import:RGB_LED")
      (libsource (lib "eagle-import") (part "EVERLIGHT_19-337"))
    )
    (comp (ref "R2")
      (value "110R")
      (footprint "eagle-import:0402")
      (libsource (lib "eagle-import") (part "R-EU_RM0402"))
    )
    (comp (ref "R3")
      (value "16R")
      (footprint "eagle-import:0402")
      (libsource (lib "eagle-import") (part "R-EU_RM0402"))
    )
    (comp (ref "R4")
      (value "24R")
      (footprint "eagle-import:0402")
      (libsource (lib "eagle-import") (part "R-EU_RM0402"))
    )
    (comp (ref "R6")
      (value "47k")
      (footprint "eagle-import:0402")
      (libsource (lib "eagle-import") (part "R-EU_RM0402"))
    )
    (comp (ref "R7")
      (value "470")
      (footprint "eagle-import:0402")
      (libsource (lib "eagle-import") (part "R-EU_RM0402"))
    )
    (comp (ref "S1")
      (value "PB")
      (footprint "eagle-import:PBTH")
      (libsource (lib "eagle-import") (part "PB"))
    )
    (comp (ref "S2")
      (value "PB")
      (footprint "eagle-import:PBTH")
      (libsource (lib "eagle-import") (part "PB"))
    )
    (comp (ref "S3")
      (value "RST")
      (footprint "eagle-import:PBTH")
      (libsource (lib "eagle-import") (part "PB"))
    )
    (comp (ref "U$1")
      (value "MOUNTHOLE_125MIL")
      (footprint "eagle-import:MOUNTHOLE_125MIL")
      (libsource (lib "eagle-import") (part "MOUNTHOLE_125MIL"))
    )
    (comp (ref "U$2")
      (value "MOUNTHOLE_125MIL")
      (footprint "eagle-import:MOUNTHOLE_125MIL")
      (libsource (lib "eagle-import") (part "MOUNTHOLE_125MIL"))
    )
    (comp (ref "U$3")
      (value "MOUNTHOLE_125MIL")
      (footprint "eagle-import:MOUNTHOLE_125MIL")
      (libsource (lib "eagle-import") (part "MOUNTHOLE_125MIL"))
    )
    (comp (ref "U$5")
      (value "MOUNTHOLE_125MIL")
      (footprint "eagle-import:MOUNTHOLE_125MIL")
      (libsource (lib "eagle-import") (part "MOUNTHOLE_125MIL"))
    )
    (comp (ref "U$6")
      (value "SILK_HEADER_LABEL")
      (footprint "eagle-import:SILK_HEADER_LABEL")
      (libsource (lib "eagle-import") (part "SILK_HEADER_LABEL"))
    )
    (comp (ref "U$7")
      (value "SILK_3V3_TAG")
      (footprint "eagle-import:SILK_3V3_TAG")
      (libsource (lib "eagle-import") (part "SILK_3V3_TAG"))
    )
    (comp (ref "U$8")
      (value "SILK_P401R_REAR")
      (footprint "eagle-import:SILK_P401R_REAR")
      (libsource (lib "eagle-import") (part "SILK_P401R_REAR"))
    )
  )
  (nets
    (net (code "1") (name "+3V3") (class "Default")
      (node (ref "C3") (pin "+") (pinfunction "+_+") (pintype "passive"))
      (node (ref "C4") (pin "1") (pinfunction "1_1") (pintype "passive"))
      (node (ref "C7") (pin "1") (pinfunction "1_1") (pintype "passive"))
      (node (ref "C9") (pin "2") (pinfunction "2_2") (pintype "passive"))
      (node (ref "J1") (pin "1") (pinfunction "1_1") (pintype "bidirectional"))
      (node (ref "J5") (pin "35") (pinfunction "35_35") (pintype "bidirectional"))
      (node (ref "J5") (pin "36") (pinfunction "36_36") (pintype "bidirectional"))
      (node (ref "J6") (pin "1") (pinfunction "1_1") (pintype "passive"))
      (node (ref "JP3") (pin "2") (pinfunction "2_2") (pintype "passive"))
      (node (ref "MSP1") (pin "13") (pinfunction "DVCC1_13") (pintype "power_in"))
      (node (ref "MSP1") (pin "73") (pinfunction "DVCC2_73") (pintype "power_in"))
      (node (ref "R1") (pin "1") (pinfunction "1_1") (pintype "passive"))
      (node (ref "R6") (pin "2") (pinfunction "2_2") (pintype "passive"))
      (node (ref "R8") (pin "1") (pinfunction "1_1") (pintype "passive"))
    )
    (net (code "2") (name "+5V") (class "Default")
      (node (ref "C14") (pin "2") (pinfunction "2_2") (pintype "passive"))
      (node (ref "J3") (pin "21") (pinfunction "1_21") (pintype "bidirectional"))
      (node (ref "J5") (pin "33") (pinfunction "33_33") (pintype "bidirectional"))
      (node (ref "J5") (pin "34") (pinfunction "34_34") (pintype "bidirectional"))
      (node (ref "J7") (pin "1") (pinfunction "1_1") (pintype "passive"))
      (node (ref "JP2") (pin "2") (pinfunction "2_2") (pintype "passive"))
    )
    (net (code "3") (name "AVCC") (class "Default")
      (node (ref "C116") (pin "2") (pinfunction "2_2") (pintype "passive"))
      (node (ref "MSP101") (pin "6") (pinfunction "6_6") (pintype "bidirectional"))
      (node (ref "R114") (pin "2") (pinfunction "2_2") (pintype "passive"))
      (node (ref "R115") (pin "1") (pinfunction "1_1") (pintype "passive"))
    )
    (net (code "4") (name "AVCCOUT") (class "Default")
      (node (ref "C115") (pin "2") (pinfunction "2_2") (pintype "passive"))
      (node (ref "MSP101") (pin "1") (pinfunction "1_1") (pintype "bidirectional"))
      (node (ref "R112") (pin "2") (pinfunction "2_2") (pintype "passive"))
      (node (ref "R113") (pin "1") (pinfunction "1_1") (pintype "passive"))
    )
    (net (code "5") (name "DCDCCAL0") (class "Default")
      (node (ref "MSP101") (pin "12") (pinfunction "12_12") (pintype "bidirectional"))
      (node (ref "R126") (pin "2") (pinfunction "2_2") (pintype "passive"))
    )
    (net (code "6") (name "DCDCCAL1") (class "Default")
      (node (ref "MSP101") (pin "2") (pinfunction "2_2") (pintype "bidirectional"))
      (node (ref "R127") (pin "2") (pinfunction "2_2") (pintype "passive"))
    )
    (net (code "7") (name "DCDCCAL2") (class "Default")
      (node (ref "MSP101") (pin "11") (pinfunction "11_11") (pintype "bidirectional"))
      (node (ref "R128") (pin "2") (pinfunction "2_2") (pintype "passive"))
    )
    (net (code "8") (name "DCDCIO0") (class "Default")
      (node (ref "IC106") (pin "P$5") (pinfunction "PQ0_P$5") (pintype "bidirectional"))
      (node (ref "MSP101") (pin "4") (pinfunction "4_4") (pintype "bidirectional"))
    )
    (net (code "9") (name "DCDCIO1") (class "Default")
      (node (ref "IC106") (pin "P$6") (pinfunction "PQ1_P$6") (pintype "bidirectional"))
      (node (ref "MSP101") (pin "5") (pinfunction "5_5") (pintype "bidirectional"))
    )
    (net (code "10") (name "DCDCPULSE") (class "Default")
      (node (ref "IC106") (pin "P$127") (pinfunction "PD6_P$127") (pintype "bidirectional"))
      (node (ref "MSP101") (pin "3") (pinfunction "3_3") (pintype "bidirectional"))
      (node (ref "R118") (pin "2") (pinfunction "2_2") (pintype "passive"))
    )
    (net (code "11") (name "DCDCRST") (class "Default")
      (node (ref "IC106") (pin "P$11") (pinfunction "PQ2_P$11") (pintype "bidirectional"))
      (node (ref "MSP101") (pin "9") (pinfunction "9_9") (pintype "bidirectional"))
      (node (ref "TP108") (pin "1") (pinfunction "1_1") (pintype "passive"))
    )
    (net (code "12") (name "DCDCTEST") (class "Default")
      (node (ref "IC106") (pin "P$27") (pinfunction "PQ3_P$27") (pintype "bidirectional"))
      (node (ref "MSP101") (pin "10") (pinfunction "10_10") (pintype "bidirectional"))
      (node (ref "TP109") (pin "1") (pinfunction "1_1") (pintype "passive"))
    )
    (net (code "13") (name "DCOR") (class "Default")
      (node (ref "MSP1") (pin "44") (pinfunction "DCOR_44") (pintype "power_in"))
      (node (ref "R5") (pin "1") (pinfunction "1_1") (pintype "passive"))
    )
    (net (code "14") (name "DEBUG_TRIGGER_0") (class "Default")
      (node (ref "IC106") (pin "P$44") (pinfunction "PF2_P$44") (pintype "bidirectional"))
    )
    (net (code "15") (name "DEBUG_TRIGGER_1") (class "Default")
      (node (ref "IC106") (pin "P$45") (pinfunction "PF3_P$45") (pintype "bidirectional"))
    )
    (net (code "16") (name "EXTERNAL_DEBUG") (class "Default")
      (node (ref "IC106") (pin "P$41") (pinfunction "PA7_P$41") (pintype "bidirectional"))
    )
    (net (code "17") (name "EXT_DEBUG_RESET") (class "Default")
      (node (ref "IC111") (pin "8") (pinfunction "3B2_8") (pintype "bidirectional"))
      (node (ref "J102") (pin "10") (pinfunction "10_10") (pintype "passive"))
    )
    (net (code "18") (name "EXT_DEBUG_TCK_SWCLK") (class "Default")
      (node (ref "IC111") (pin "4") (pinfunction "2B2_4") (pintype "bidirectional"))
      (node (ref "J102") (pin "4") (pinfunction "4_4") (pintype "passive"))
    )
    (net (code "19") (name "EXT_DEBUG_TDI") (class "Default")
      (node (ref "J102") (pin "8") (pinfunction "8_8") (pintype "passive"))
      (node (ref "S101") (pin "4") (pinfunction "L3_4") (pintype "bidirectional"))
    )
    (net (code "20") (name "EXT_DEBUG_TDO_SWO") (class "Default")
      (node (ref "IC111") (pin "11") (pinfunction "4B2_11") (pintype "bidirectional"))
      (node (ref "J102") (pin "6") (pinfunction "6_6") (pintype "passive"))
    )
    (net (code "21") (name "EXT_DEBUG_TMS_SWDIO") (class "Default")
      (node (ref "IC111") (pin "1") (pinfunction "1B2_1") (pintype "bidirectional"))
      (node (ref "J102") (pin "2") (pinfunction "2_2") (pintype "passive"))
    )
    (net (code "22") (name "GND") (class "Default")
      (node (ref "C1") (pin "2") (pinfunction "2_2") (pintype "passive"))
      (node (ref "C10") (pin "2") (pinfunction "2_2") (pintype "passive"))
      (node (ref "C101") (pin "2") (pinfunction "2_2") (pintype "passive"))
      (node (ref "C102") (pin "2") (pinfunction "2_2") (pintype "passive"))
      (node (ref "C103") (pin "2") (pinfunction "2_2") (pintype "passive"))
      (node (ref "C104") (pin "2") (pinfunction "2_2") (pintype "passive"))
      (node (ref "C105") (pin "2") (pinfunction "2_2") (pintype "passive"))
      (node (ref "C106") (pin "-") (pinfunction "-_-") (pintype "passive"))
      (node (ref "C107") (pin "2") (pinfunction "2_2") (pintype "passive"))
      (node (ref "C108") (pin "2") (pinfunction "2_2") (pintype "passive"))
      (node (ref "C109") (pin "2") (pinfunction "2_2") (pintype "passive"))
      (node (ref "C11") (pin "2") (pinfunction "2_2") (pintype "passive"))
      (node (ref "C110") (pin "2") (pinfunction "2_2") (pintype "passive"))
      (node (ref "C111") (pin "2") (pinfunction "2_2") (pintype "passive"))
      (node (ref "C112") (pin "2") (pinfunction "2_2") (pintype "passive"))
      (node (ref "C113") (pin "2") (pinfunction "2_2") (pintype "passive"))
      (node (ref "C114") (pin "2") (pinfunction "2_2") (pintype "passive"))
      (node (ref "C115") (pin "1") (pinfunction "1_1") (pintype "passive"))
      (node (ref "C116") (pin "1") (pinfunction "1_1") (pintype "passive"))
      (node (ref "C117") (pin "2") (pinfunction "2_2") (pintype "passive"))
      (node (ref "C118") (pin "2") (pinfunction "2_2") (pintype "passive"))
      (node (ref "C119") (pin "2") (pinfunction "2_2") (pintype "passive"))
      (node (ref "C12") (pin "2") (pinfunction "2_2") (pintype "passive"))
      (node (ref "C120") (pin "2") (pinfunction "2_2") (pintype "passive"))
      (node (ref "C121") (pin "2") (pinfunction "2_2") (pintype "passive"))
      (node (ref "C122") (pin "2") (pinfunction "2_2") (pintype "passive"))
      (node (ref "C123") (pin "2") (pinfunction "2_2") (pintype "passive"))
      (node (ref "C124") (pin "2") (pinfunction "2_2") (pintype "passive"))
      (node (ref "C125") (pin "2") (pinfunction "2_2") (pintype "passive"))
      (node (ref "C126") (pin "2") (pinfunction "2_2") (pintype "passive"))
      (node (ref "C127") (pin "2") (pinfunction "2_2") (pintype "passive"))
      (node (ref "C128") (pin "-") (pinfunction "-_-") (pintype "passive"))
      (node (ref "C129") (pin "2") (pinfunction "2_2") (pintype "passive"))
      (node (ref "C13") (pin "2") (pinfunction "2_2") (pintype "passive"))
      (node (ref "C130") (pin "1") (pinfunction "1_1") (pintype "passive"))
      (node (ref "C131") (pin "2") (pinfunction "2_2") (pintype "passive"))
      (node (ref "C132") (pin "1") (pinfunction "1_1") (pintype "passive"))
      (node (ref "C133") (pin "2") (pinfunction "2_2") (pintype "passive"))
      (node (ref "C134") (pin "2") (pinfunction "2_2") (pintype "passive"))
      (node (ref "C135") (pin "2") (pinfunction "2_2") (pintype "passive"))
      (node (ref "C136") (pin "2") (pinfunction "2_2") (pintype "passive"))
      (node (ref "C137") (pin "2") (pinfunction "2_2") (pintype "passive"))
      (node (ref "C138") (pin "2") (pinfunction "2_2") (pintype "passive"))
      (node (ref "C139") (pin "2") (pinfunction "2_2") (pintype "passive"))
      (node (ref "C14") (pin "1") (pinfunction "1_1") (pintype "passive"))
      (node (ref "C140") (pin "-") (pinfunction "-_-") (pintype "passive"))
      (node (ref "C141") (pin "2") (pinfunction "2_2") (pintype "passive"))
      (node (ref "C142") (pin "2") (pinfunction "2_2") (pintype "passive"))
      (node (ref "C143") (pin "2") (pinfunction "2_2") (pintype "passive"))
      (node (ref "C144") (pin "2") (pinfunction "2_2") (pintype "passive"))
      (node (ref "C145") (pin "2") (pinfunction "2_2") (pintype "passive"))
      (node (ref "C146") (pin "2") (pinfunction "2_2") (pintype "passive"))
      (node (ref "C147") (pin "2") (pinfunction "2_2") (pintype "passive"))
      (node (ref "C148") (pin "2") (pinfunction "2_2") (pintype "passive"))
      (node (ref "C149") (pin "2") (pinfunction "2_2") (pintype "passive"))
      (node (ref "C2") (pin "2") (pinfunction "2_2") (pintype "passive"))
      (node (ref "C3") (pin "-") (pinfunction "-_-") (pintype "passive"))
      (node (ref "C4") (pin "2") (pinfunction "2_2") (pintype "passive"))
      (node (ref "C5") (pin "2") (pinfunction "2_2") (pintype "passive"))
      (node (ref "C6") (pin "2") (pinfunction "2_2") (pintype "passive"))
      (node (ref "C7") (pin "2") (pinfunction "2_2") (pintype "passive"))
      (node (ref "C8") (pin "2") (pinfunction "2_2") (pintype "passive"))
      (node (ref "C9") (pin "1") (pinfunction "1_1") (pintype "passive"))
      (node (ref "D102") (pin "1") (pinfunction "A1_1") (pintype "passive"))
      (node (ref "D102") (pin "2") (pinfunction "A2_2") (pintype "passive"))
      (node (ref "IC101") (pin "4") (pinfunction "GND_4") (pintype "bidirectional"))
      (node (ref "IC101") (pin "9") (pinfunction "PAD_9") (pintype "bidirectional"))
      (node (ref "IC102") (pin "3") (pinfunction "GND_3") (pintype "power_in"))
      (node (ref "IC103") (pin "2") (pinfunction "GND_2") (pintype "bidirectional"))
      (node (ref "IC104") (pin "2") (pinfunction "GND_2") (pintype "power_in"))
      (node (ref "IC105") (pin "1") (pinfunction "REFCLK_1") (pintype "input"))
      (node (ref "IC105") (pin "33") (pinfunction "EPAD_33") (pintype "passive"))
      (node (ref "IC106") (pin "P$10") (pinfunction "GNDA_P$10") (pintype "bidirectional"))
      (node (ref "IC106") (pin "P$114") (pinfunction "GND_P$114") (pintype "bidirectional"))
      (node (ref "IC106") (pin "P$17") (pinfunction "GND_P$17") (pintype "bidirectional"))
      (node (ref "IC106") (pin "P$48") (pinfunction "GND_P$48") (pintype "bidirectional"))
      (node (ref "IC106") (pin "P$55") (pinfunction "GND_P$55") (pintype "bidirectional"))
      (node (ref "IC106") (pin "P$58") (pinfunction "GND_P$58") (pintype "bidirectional"))
      (node (ref "IC106") (pin "P$64") (pinfunction "~{WAKE}_P$64") (pintype "bidirectional"))
      (node (ref "IC106") (pin "P$66") (pinfunction "XOSC0_P$66") (pintype "bidirectional"))
      (node (ref "IC106") (pin "P$80") (pinfunction "GND_P$80") (pintype "bidirectional"))
      (node (ref "IC107") (pin "1") (pinfunction "A_1") (pintype "passive"))
      (node (ref "IC108") (pin "1") (pinfunction "*1OE_1") (pintype "input"))
      (node (ref "IC108") (pin "10") (pinfunction "GND_2_10") (pintype "power_in"))
      (node (ref "IC108") (pin "11") (pinfunction "GND_11") (pintype "power_in"))
      (node (ref "IC108") (pin "16") (pinfunction "*2OE_16") (pintype "input"))
      (node (ref "IC109") (pin "1") (pinfunction "*1OE_1") (pintype "input"))
      (node (ref "IC109") (pin "10") (pinfunction "GND_2_10") (pintype "power_in"))
      (node (ref "IC109") (pin "11") (pinfunction "GND_11") (pintype "power_in"))
      (node (ref "IC109") (pin "16") (pinfunction "*2OE_16") (pintype "input"))
      (node (ref "IC110") (pin "1") (pinfunction "*1OE_1") (pintype "input"))
      (node (ref "IC110") (pin "10") (pinfunction "GND_2_10") (pintype "power_in"))
      (node (ref "IC110") (pin "11") (pinfunction "GND_11") (pintype "power_in"))
      (node (ref "IC110") (pin "16") (pinfunction "*2OE_16") (pintype "input"))
      (node (ref "IC110") (pin "5") (pinfunction "2DIR_5") (pintype "input"))
      (node (ref "IC111") (pin "13") (pinfunction "~{OE}_13") (pintype "bidirectional"))
      (node (ref "IC111") (pin "6") (pinfunction "GND_6") (pintype "bidirectional"))
      (node (ref "J101") (pin "GND") (pinfunction "GND_GND") (pintype "input"))
      (node (ref "J102") (pin "3") (pinfunction "3_3") (pintype "passive"))
      (node (ref "J102") (pin "5") (pinfunction "5_5") (pintype "passive"))
      (node (ref "J102") (pin "7") (pinfunction "7_7") (pintype "passive"))
      (node (ref "J102") (pin "9") (pinfunction "9_9") (pintype "passive"))
      (node (ref "J103") (pin "7") (pinfunction "7_7") (pintype "passive"))
      (node (ref "J2") (pin "20") (pinfunction "1_20") (pintype "bidirectional"))
      (node (ref "J3") (pin "22") (pinfunction "2_22") (pintype "bidirectional"))
      (node (ref "J5") (pin "37") (pinfunction "37_37") (pintype "bidirectional"))
      (node (ref "J5") (pin "38") (pinfunction "38_38") (pintype "bidirectional"))
      (node (ref "J6") (pin "2") (pinfunction "2_2") (pintype "passive"))
      (node (ref "J6") (pin "3") (pinfunction "3_3") (pintype "passive"))
      (node (ref "J7") (pin "2") (pinfunction "2_2") (pintype "passive"))
      (node (ref "J7") (pin "3") (pinfunction "3_3") (pintype "passive"))
      (node (ref "LED1") (pin "C") (pinfunction "C_C") (pintype "passive"))
      (node (ref "LED101") (pin "C") (pinfunction "C_C") (pintype "passive"))
      (node (ref "LED102") (pin "C") (pinfunction "C_C") (pintype "passive"))
      (node (ref "LED2") (pin "1") (pinfunction "BC_1") (pintype "passive"))
      (node (ref "LED2") (pin "2") (pinfunction "RC_2") (pintype "passive"))
      (node (ref "LED2") (pin "3") (pinfunction "GC_3") (pintype "passive"))
      (node (ref "MSP1") (pin "15") (pinfunction "DVSS1_15") (pintype "power_in"))
      (node (ref "MSP1") (pin "40") (pinfunction "AVSS3_40") (pintype "power_in"))
      (node (ref "MSP1") (pin "43") (pinfunction "AVSS1_43") (pintype "power_in"))
      (node (ref "MSP1") (pin "72") (pinfunction "DVSS2_72") (pintype "power_in"))
      (node (ref "MSP1") (pin "82") (pinfunction "DVSS3_82") (pintype "power_in"))
      (node (ref "MSP1") (pin "84") (pinfunction "AVSS2_84") (pintype "power_in"))
      (node (ref "MSP101") (pin "13") (pinfunction "13_13") (pintype "bidirectional"))
      (node (ref "MSP101") (pin "14") (pinfunction "14_14") (pintype "bidirectional"))
      (node (ref "MSP101") (pin "TP") (pinfunction "TP_TP") (pintype "bidirectional"))
      (node (ref "Q1") (pin "P3") (pinfunction "GND_P3") (pintype "power_in"))
      (node (ref "R101") (pin "1") (pinfunction "1_1") (pintype "passive"))
      (node (ref "R107") (pin "2") (pinfunction "2_2") (pintype "passive"))
      (node (ref "R108") (pin "1") (pinfunction "1_1") (pintype "passive"))
      (node (ref "R109") (pin "1") (pinfunction "1_1") (pintype "passive"))
      (node (ref "R110") (pin "1") (pinfunction "1_1") (pintype "passive"))
      (node (ref "R113") (pin "2") (pinfunction "2_2") (pintype "passive"))
      (node (ref "R115") (pin "2") (pinfunction "2_2") (pintype "passive"))
      (node (ref "R119") (pin "2") (pinfunction "2_2") (pintype "passive"))
      (node (ref "R123") (pin "2") (pinfunction "2_2") (pintype "passive"))
      (node (ref "R133") (pin "1") (pinfunction "1_1") (pintype "passive"))
      (node (ref "R136") (pin "1") (pinfunction "1_1") (pintype "passive"))
      (node (ref "R139") (pin "1") (pinfunction "1_1") (pintype "passive"))
      (node (ref "R5") (pin "2") (pinfunction "2_2") (pintype "passive"))
      (node (ref "S1") (pin "2") (pinfunction "S_2") (pintype "passive"))
      (node (ref "S101") (pin "3") (pinfunction "L2_3") (pintype "bidirectional"))
      (node (ref "S2") (pin "2") (pinfunction "S_2") (pintype "passive"))
      (node (ref "S3") (pin "1") (pinfunction "P_1") (pintype "passive"))
      (node (ref "TP101") (pin "1") (pinfunction "1_1") (pintype "passive"))
    )
    (net (code "23") (name "HOSTSCL") (class "Default")
      (node (ref "IC106") (pin "P$49") (pinfunction "PG0_P$49") (pintype "bidirectional"))
      (node (ref "MSP101") (pin "7") (pinfunction "7_7") (pintype "bidirectional"))
      (node (ref "R117") (pin "2") (pinfunction "2_2") (pintype "passive"))
    )
    (net (code "24") (name "HOSTSDA") (class "Default")
      (node (ref "IC106") (pin "P$50") (pinfunction "PG1_P$50") (pintype "bidirectional"))
      (node (ref "MSP101") (pin "8") (pinfunction "8_8") (pintype "bidirectional"))
      (node (ref "R116") (pin "2") (pinfunction "2_2") (pintype "passive"))
    )
    (net (code "25") (name "IRSTN") (class "Default")
      (node (ref "R102") (pin "1") (pinfunction "1_1") (pintype "passive"))
      (node (ref "TP106") (pin "1") (pinfunction "1_1") (pintype "passive"))
    )
    (net (code "26") (name "ITCK") (class "Default")
      (node (ref "IC106") (pin "P$100") (pinfunction "PC0_P$100") (pintype "bidirectional"))
      (node (ref "R129") (pin "1") (pinfunction "1_1") (pintype "passive"))
      (node (ref "TP103") (pin "1") (pinfunction "1_1") (pintype "passive"))
    )
    (net (code "27") (name "ITDI") (class "Default")
      (node (ref "IC106") (pin "P$98") (pinfunction "PC2_P$98") (pintype "bidirectional"))
      (node (ref "TP105") (pin "1") (pinfunction "1_1") (pintype "passive"))
    )
    (net (code "28") (name "ITDO") (class "Default")
      (node (ref "IC106") (pin "P$97") (pinfunction "PC3_P$97") (pintype "bidirectional"))
      (node (ref "TP104") (pin "1") (pinfunction "1_1") (pintype "passive"))
    )
    (net (code "29") (name "ITMS") (class "Default")
      (node (ref "IC106") (pin "P$99") (pinfunction "PC1_P$99") (pintype "bidirectional"))
      (node (ref "R125") (pin "1") (pinfunction "1_1") (pintype "passive"))
      (node (ref "TP102") (pin "1") (pinfunction "1_1") (pintype "passive"))
    )
    (net (code "30") (name "JTAG_SELECT") (class "Default")
      (node (ref "IC111") (pin "15") (pinfunction "SEL_15") (pintype "bidirectional"))
      (node (ref "S101") (pin "2") (pinfunction "C1_2") (pintype "bidirectional"))
    )
    (net (code "31") (name "LED0") (class "Default")
      (node (ref "IC106") (pin "P$3") (pinfunction "PD2_P$3") (pintype "bidirectional"))
      (node (ref "R111") (pin "1") (pinfunction "1_1") (pintype "passive"))
    )
    (net (code "32") (name "LED1") (class "Default")
      (node (ref "IC106") (pin "P$4") (pinfunction "PD3_P$4") (pintype "bidirectional"))
      (node (ref "R124") (pin "1") (pinfunction "1_1") (pintype "passive"))
    )
    (net (code "33") (name "Net-(D101-A1)") (class "Default")
      (node (ref "D101") (pin "1") (pinfunction "A1_1") (pintype "passive"))
      (node (ref "D101") (pin "2") (pinfunction "A2_2") (pintype "passive"))
      (node (ref "R118") (pin "1") (pinfunction "1_1") (pintype "passive"))
      (node (ref "T102") (pin "B") (pinfunction "B_B") (pintype "passive"))
    )
    (net (code "34") (name "Net-(D101-C)") (class "Default")
      (node (ref "D101") (pin "3") (pinfunction "C_3") (pintype "passive"))
      (node (ref "R120") (pin "2") (pinfunction "2_2") (pintype "passive"))
      (node (ref "T101") (pin "1") (pinfunction "G_1") (pintype "passive"))
      (node (ref "T102") (pin "C") (pinfunction "C_C") (pintype "passive"))
    )
    (net (code "35") (name "Net-(D102-C)") (class "Default")
      (node (ref "D102") (pin "3") (pinfunction "C_3") (pintype "passive"))
      (node (ref "L101") (pin "1") (pinfunction "1_1") (pintype "passive"))
      (node (ref "T101") (pin "3") (pinfunction "D_3") (pintype "passive"))
    )
    (net (code "36") (name "Net-(IC101-NR)") (class "Default")
      (node (ref "C125") (pin "1") (pinfunction "1_1") (pintype "passive"))
      (node (ref "IC101") (pin "3") (pinfunction "NR_3") (pintype "bidirectional"))
    )
    (net (code "37") (name "Net-(IC105-DM)") (class "Default")
      (node (ref "IC105") (pin "19") (pinfunction "DM_19") (pintype "bidirectional"))
      (node (ref "R122") (pin "1") (pinfunction "1_1") (pintype "passive"))
    )
    (net (code "38") (name "Net-(IC105-DP)") (class "Default")
      (node (ref "IC105") (pin "18") (pinfunction "DP_18") (pintype "bidirectional"))
      (node (ref "R121") (pin "1") (pinfunction "1_1") (pintype "passive"))
    )
    (net (code "39") (name "Net-(IC105-ID)") (class "Default")
      (node (ref "IC105") (pin "23") (pinfunction "ID_23") (pintype "bidirectional"))
      (node (ref "R130") (pin "2") (pinfunction "2_2") (pintype "passive"))
    )
    (net (code "40") (name "Net-(IC105-VDD15)") (class "Default")
      (node (ref "C139") (pin "1") (pinfunction "1_1") (pintype "passive"))
      (node (ref "IC105") (pin "12") (pinfunction "VDD15_12") (pintype "power_in"))
    )
    (net (code "41") (name "Net-(IC105-VDD18_2)") (class "Default")
      (node (ref "C134") (pin "1") (pinfunction "1_1") (pintype "passive"))
      (node (ref "IC105") (pin "28") (pinfunction "VDD18_2_28") (pintype "power_in"))
    )
    (net (code "42") (name "Net-(IC105-VDD33)") (class "Default")
      (node (ref "C137") (pin "1") (pinfunction "1_1") (pintype "passive"))
      (node (ref "IC105") (pin "20") (pinfunction "VDD33_20") (pintype "power_in"))
    )
    (net (code "43") (name "Net-(IC106A-PB0)") (class "Default")
      (node (ref "IC106") (pin "P$95") (pinfunction "PB0_P$95") (pintype "bidirectional"))
      (node (ref "R131") (pin "2") (pinfunction "2_2") (pintype "passive"))
    )
    (net (code "44") (name "Net-(IC106A-PK4)") (class "Default")
      (node (ref "IC106") (pin "P$63") (pinfunction "PK4_P$63") (pintype "bidirectional"))
      (node (ref "R108") (pin "2") (pinfunction "2_2") (pintype "passive"))
    )
    (net (code "45") (name "Net-(IC106A-PK5)") (class "Default")
      (node (ref "IC106") (pin "P$62") (pinfunction "PK5_P$62") (pintype "bidirectional"))
      (node (ref "R109") (pin "2") (pinfunction "2_2") (pintype "passive"))
    )
    (net (code "46") (name "Net-(IC106A-PK6)") (class "Default")
      (node (ref "IC106") (pin "P$61") (pinfunction "PK6_P$61") (pintype "bidirectional"))
      (node (ref "R110") (pin "2") (pinfunction "2_2") (pintype "passive"))
    )
    (net (code "47") (name "Net-(IC106A-PL6)") (class "Default")
      (node (ref "IC106") (pin "P$94") (pinfunction "PL6_P$94") (pintype "bidirectional"))
      (node (ref "R137") (pin "2") (pinfunction "2_2") (pintype "passive"))
    )
    (net (code "48") (name "Net-(IC106A-PL7)") (class "Default")
      (node (ref "IC106") (pin "P$93") (pinfunction "PL7_P$93") (pintype "bidirectional"))
      (node (ref "R138") (pin "2") (pinfunction "2_2") (pintype "passive"))
    )
    (net (code "49") (name "Net-(IC106B-OSC1)") (class "Default")
      (node (ref "IC106") (pin "P$89") (pinfunction "OSC1_P$89") (pintype "bidirectional"))
      (node (ref "R106") (pin "2") (pinfunction "2_2") (pintype "passive"))
    )
    (net (code "50") (name "Net-(IC106B-RBIAS)") (class "Default")
      (node (ref "IC106") (pin "P$59") (pinfunction "RBIAS_P$59") (pintype "bidirectional"))
      (node (ref "R139") (pin "2") (pinfunction "2_2") (pintype "passive"))
    )
    (net (code "51") (name "Net-(J102-Pad1)") (class "Default")
      (node (ref "J102") (pin "1") (pinfunction "1_1") (pintype "passive"))
      (node (ref "R8") (pin "2") (pinfunction "2_2") (pintype "passive"))
    )
    (net (code "52") (name "Net-(JP8-Pad2)") (class "Default")
      (node (ref "JP8") (pin "2") (pinfunction "2_2") (pintype "passive"))
      (node (ref "R7") (pin "1") (pinfunction "1_1") (pintype "passive"))
    )
    (net (code "53") (name "Net-(JP9-Pad2)") (class "Default")
      (node (ref "JP9") (pin "2") (pinfunction "2_2") (pintype "passive"))
      (node (ref "R2") (pin "1") (pinfunction "1_1") (pintype "passive"))
    )
    (net (code "54") (name "Net-(JP10-Pad2)") (class "Default")
      (node (ref "JP10") (pin "2") (pinfunction "2_2") (pintype "passive"))
      (node (ref "R3") (pin "1") (pinfunction "1_1") (pintype "passive"))
    )
    (net (code "55") (name "Net-(JP11-Pad2)") (class "Default")
      (node (ref "JP11") (pin "2") (pinfunction "2_2") (pintype "passive"))
      (node (ref "R4") (pin "1") (pinfunction "1_1") (pintype "passive"))
    )
    (net (code "56") (name "Net-(LED1-PadA)") (class "Default")
      (node (ref "LED1") (pin "A") (pinfunction "A_A") (pintype "passive"))
      (node (ref "R7") (pin "2") (pinfunction "2_2") (pintype "passive"))
    )
    (net (code "57") (name "Net-(LED2-BA)") (class "Default")
      (node (ref "LED2") (pin "4") (pinfunction "BA_4") (pintype "passive"))
      (node (ref "R4") (pin "2") (pinfunction "2_2") (pintype "passive"))
    )
    (net (code "58") (name "Net-(LED2-GA)") (class "Default")
      (node (ref "LED2") (pin "6") (pinfunction "GA_6") (pintype "passive"))
      (node (ref "R3") (pin "2") (pinfunction "2_2") (pintype "passive"))
    )
    (net (code "59") (name "Net-(LED2-RA)") (class "Default")
      (node (ref "LED2") (pin "5") (pinfunction "RA_5") (pintype "passive"))
      (node (ref "R2") (pin "2") (pinfunction "2_2") (pintype "passive"))
    )
    (net (code "60") (name "Net-(LED101-PadA)") (class "Default")
      (node (ref "LED101") (pin "A") (pinfunction "A_A") (pintype "passive"))
      (node (ref "R111") (pin "2") (pinfunction "2_2") (pintype "passive"))
    )
    (net (code "61") (name "Net-(LED102-PadA)") (class "Default")
      (node (ref "LED102") (pin "A") (pinfunction "A_A") (pintype "passive"))
      (node (ref "R124") (pin "2") (pinfunction "2_2") (pintype "passive"))
    )
    (net (code "62") (name "Net-(MSP1-AVCC1)") (class "Default")
      (node (ref "C1") (pin "1") (pinfunction "1_1") (pintype "passive"))
      (node (ref "C2") (pin "1") (pinfunction "1_1") (pintype "passive"))
      (node (ref "MSP1") (pin "45") (pinfunction "AVCC1_45") (pintype "power_in"))
      (node (ref "MSP1") (pin "87") (pinfunction "AVCC2_87") (pintype "power_in"))
      (node (ref "R1") (pin "2") (pinfunction "2_2") (pintype "passive"))
    )
    (net (code "63") (name "Net-(MSP1-PJ.0{slash}LFXIN)") (class "Default")
      (node (ref "C5") (pin "1") (pinfunction "1_1") (pintype "passive"))
      (node (ref "MSP1") (pin "41") (pinfunction "PJ.0/LFXIN_41") (pintype "power_in"))
      (node (ref "Q1") (pin "P2") (pinfunction "2_P2") (pintype "bidirectional"))
    )
    (net (code "64") (name "Net-(MSP1-PJ.1{slash}LFXOUT)") (class "Default")
      (node (ref "C6") (pin "1") (pinfunction "1_1") (pintype "passive"))
      (node (ref "MSP1") (pin "42") (pinfunction "PJ.1/LFXOUT_42") (pintype "power_in"))
      (node (ref "Q1") (pin "P1") (pinfunction "1_P1") (pintype "bidirectional"))
    )
    (net (code "65") (name "Net-(MSP1-PJ.2{slash}HFXOUT)") (class "Default")
      (node (ref "C11") (pin "1") (pinfunction "1_1") (pintype "passive"))
      (node (ref "MSP1") (pin "85") (pinfunction "PJ.2/HFXOUT_85") (pintype "power_in"))
      (node (ref "Q2") (pin "1") (pinfunction "1_1") (pintype "passive"))
    )
    (net (code "66") (name "Net-(MSP1-PJ.3{slash}HFXIN)") (class "Default")
      (node (ref "C12") (pin "1") (pinfunction "1_1") (pintype "passive"))
      (node (ref "MSP1") (pin "86") (pinfunction "PJ.3/HFXIN_86") (pintype "power_in"))
      (node (ref "Q2") (pin "3") (pinfunction "2_3") (pintype "passive"))
    )
    (net (code "67") (name "Net-(Q101-OSC0)") (class "Default")
      (node (ref "C101") (pin "1") (pinfunction "1_1") (pintype "passive"))
      (node (ref "Q101") (pin "1") (pinfunction "OSC0_1") (pintype "bidirectional"))
      (node (ref "R106") (pin "1") (pinfunction "1_1") (pintype "passive"))
    )
    (net (code "68") (name "Net-(R119-Pad1)") (class "Default")
      (node (ref "R119") (pin "1") (pinfunction "1_1") (pintype "passive"))
      (node (ref "T102") (pin "E") (pinfunction "E_E") (pintype "passive"))
    )
    (net (code "69") (name "OSC0") (class "Default")
      (node (ref "C102") (pin "1") (pinfunction "1_1") (pintype "passive"))
      (node (ref "IC106") (pin "P$88") (pinfunction "OSC0_P$88") (pintype "bidirectional"))
      (node (ref "Q101") (pin "3") (pinfunction "OSC1_3") (pintype "bidirectional"))
    )
    (net (code "70") (name "P1.0_LED1") (class "Default")
      (node (ref "JP8") (pin "1") (pinfunction "1_1") (pintype "passive"))
      (node (ref "MSP1") (pin "4") (pinfunction "P1.0/UCA0STE_4") (pintype "power_in"))
    )
    (net (code "71") (name "P1.1_BUTTON1") (class "Default")
      (node (ref "MSP1") (pin "5") (pinfunction "P1.1/UCA0CLK_5") (pintype "power_in"))
      (node (ref "S1") (pin "1") (pinfunction "P_1") (pintype "passive"))
    )
    (net (code "72") (name "P1.2_BCLUART_RXD") (class "Default")
      (node (ref "JP4.3") (pin "2") (pinfunction "2_2") (pintype "passive"))
      (node (ref "MSP1") (pin "6") (pinfunction "P1.2/UCA0RXD/UCA0SOMI_6") (pintype "power_in"))
    )
    (net (code "73") (name "P1.3_BCLUART_TXD") (class "Default")
      (node (ref "JP4.4") (pin "2") (pinfunction "2_2") (pintype "passive"))
      (node (ref "MSP1") (pin "7") (pinfunction "P1.3/UCA0TXD/UCA0SIMO_7") (pintype "power_in"))
    )
    (net (code "74") (name "P1.4_BUTTON2") (class "Default")
      (node (ref "MSP1") (pin "8") (pinfunction "P1.4/UCB0STE_8") (pintype "power_in"))
      (node (ref "S2") (pin "1") (pinfunction "P_1") (pintype "passive"))
    )
    (net (code "75") (name "P1.5_SPICLK_J1.7") (class "Default")
      (node (ref "J1") (pin "7") (pinfunction "7_7") (pintype "bidirectional"))
      (node (ref "MSP1") (pin "9") (pinfunction "P1.5/UCB0CLK_9") (pintype "power_in"))
    )
    (net (code "76") (name "P1.6_SPIMOSI_J2.15") (class "Default")
      (node (ref "J2") (pin "15") (pinfunction "6_15") (pintype "bidirectional"))
      (node (ref "MSP1") (pin "10") (pinfunction "P1.6/UCB0SIMO/UCB0SDA_10") (pintype "power_in"))
    )
    (net (code "77") (name "P1.7_SPIMISO_J2.14") (class "Default")
      (node (ref "J2") (pin "14") (pinfunction "7_14") (pintype "bidirectional"))
      (node (ref "MSP1") (pin "11") (pinfunction "P1.7/UCB0SOMI/UCB0SCL_11") (pintype "power_in"))
    )
    (net (code "78") (name "P2.0_RGBLED_RED") (class "Default")
      (node (ref "JP9") (pin "1") (pinfunction "1_1") (pintype "passive"))
      (node (ref "MSP1") (pin "16") (pinfunction "P2.0/PM_UCA1STE_16") (pintype "power_in"))
    )
    (net (code "79") (name "P2.1_RGBLED_GREEN") (class "Default")
      (node (ref "JP10") (pin "1") (pinfunction "1_1") (pintype "passive"))
      (node (ref "MSP1") (pin "17") (pinfunction "P2.1/PM_UCA1CLK_17") (pintype "power_in"))
    )
    (net (code "80") (name "P2.2_RGBLED_BLUE") (class "Default")
      (node (ref "JP11") (pin "1") (pinfunction "1_1") (pintype "passive"))
      (node (ref "MSP1") (pin "18") (pinfunction "P2.2/PM_UCA1RXD/PM_UCA1SOMI_18") (pintype "power_in"))
    )
    (net (code "81") (name "P2.3_IO_J4.34") (class "Default")
      (node (ref "J4") (pin "34") (pinfunction "7_34") (pintype "bidirectional"))
      (node (ref "MSP1") (pin "19") (pinfunction "P2.3/PM_UCA1TXD/PM_UCA1SIMO_19") (pintype "power_in"))
    )
    (net (code "82") (name "P2.4_PWM_J4.38") (class "Default")
      (node (ref "J4") (pin "38") (pinfunction "3_38") (pintype "bidirectional"))
      (node (ref "MSP1") (pin "20") (pinfunction "P2.4/PM_TA0.1_20") (pintype "power_in"))
    )
    (net (code "83") (name "P2.5_PWM_J2.19") (class "Default")
      (node (ref "J2") (pin "19") (pinfunction "2_19") (pintype "bidirectional"))
      (node (ref "MSP1") (pin "21") (pinfunction "P2.5/PM_TA0.2_21") (pintype "power_in"))
    )
    (net (code "84") (name "P2.6_PWM_J4.39") (class "Default")
      (node (ref "J4") (pin "39") (pinfunction "2_39") (pintype "bidirectional"))
      (node (ref "MSP1") (pin "22") (pinfunction "P2.6/PM_TA0.3_22") (pintype "power_in"))
    )
    (net (code "85") (name "P2.7_PWM_J4.40") (class "Default")
      (node (ref "J4") (pin "40") (pinfunction "1_40") (pintype "bidirectional"))
      (node (ref "MSP1") (pin "23") (pinfunction "P2.7/PM_TA0.4_23") (pintype "power_in"))
    )
    (net (code "86") (name "P3.0_IO_J2.18") (class "Default")
      (node (ref "J2") (pin "18") (pinfunction "3_18") (pintype "bidirectional"))
      (node (ref "MSP1") (pin "32") (pinfunction "P3.0/PM_UCA2STE_32") (pintype "power_in"))
    )
    (net (code "87") (name "P3.1_BCLUART_RTS") (class "Default")
      (node (ref "JP4.1") (pin "2") (pinfunction "2_2") (pintype "passive"))
      (node (ref "MSP1") (pin "33") (pinfunction "P3.1/PM_UCA2CLK_33") (pintype "power_in"))
    )
    (net (code "88") (name "P3.2_URXD_J1.3") (class "Default")
      (node (ref "J1") (pin "3") (pinfunction "3_3") (pintype "bidirectional"))
      (node (ref "MSP1") (pin "34") (pinfunction "P3.2/PM_UCA2RXD/PM_UCA2SOMI_34") (pintype "power_in"))
    )
    (net (code "89") (name "P3.3_UTXD_J1.4") (class "Default")
      (node (ref "J1") (pin "4") (pinfunction "4_4") (pintype "bidirectional"))
      (node (ref "MSP1") (pin "35") (pinfunction "P3.3/PM_UCA2TXD/PM_UCA2SIMO_35") (pintype "power_in"))
    )
    (net (code "90") (name "P3.4_BCLUART_CTS") (class "Default")
      (node (ref "JP4.2") (pin "2") (pinfunction "2_2") (pintype "passive"))
      (node (ref "MSP1") (pin "36") (pinfunction "P3.4/PM_UCB2STE_36") (pintype "power_in"))
    )
    (net (code "91") (name "P3.5_IO_J4.32") (class "Default")
      (node (ref "J4") (pin "32") (pinfunction "9_32") (pintype "bidirectional"))
      (node (ref "MSP1") (pin "37") (pinfunction "P3.5/PM_UCB2CLK_37") (pintype "power_in"))
    )
    (net (code "92") (name "P3.6_IO_J2.11") (class "Default")
      (node (ref "J2") (pin "11") (pinfunction "10_11") (pintype "bidirectional"))
      (node (ref "MSP1") (pin "38") (pinfunction "P3.6/PM_UCB2SIMO/PM_UCB2SDA_38") (pintype "power_in"))
    )
    (net (code "93") (name "P3.7_IO_J4.31") (class "Default")
      (node (ref "J4") (pin "31") (pinfunction "10_31") (pintype "bidirectional"))
      (node (ref "MSP1") (pin "39") (pinfunction "P3.7/PM_UCB2SOMI/PM_UCB2SCL_39") (pintype "power_in"))
    )
    (net (code "94") (name "P4.0_A13_J3.24") (class "Default")
      (node (ref "J3") (pin "24") (pinfunction "4_24") (pintype "bidirectional"))
      (node (ref "MSP1") (pin "56") (pinfunction "P4.0/A13_56") (pintype "power_in"))
    )
    (net (code "95") (name "P4.1_IO_J1.5") (class "Default")
      (node (ref "J1") (pin "5") (pinfunction "5_5") (pintype "bidirectional"))
      (node (ref "MSP1") (pin "57") (pinfunction "P4.1/A12_57") (pintype "power_in"))
    )
    (net (code "96") (name "P4.2_A11_J3.25") (class "Default")
      (node (ref "J3") (pin "25") (pinfunction "5_25") (pintype "bidirectional"))
      (node (ref "MSP1") (pin "58") (pinfunction "P4.2/ACLK/TA2CLK/A11_58") (pintype "power_in"))
    )
    (net (code "97") (name "P4.3_A10_J1.6") (class "Default")
      (node (ref "J1") (pin "6") (pinfunction "6_6") (pintype "bidirectional"))
      (node (ref "MSP1") (pin "59") (pinfunction "P4.3/MCLK/RTCCLK/A10_59") (pintype "power_in"))
    )
    (net (code "98") (name "P4.4_A9_J3.26") (class "Default")
      (node (ref "J3") (pin "26") (pinfunction "6_26") (pintype "bidirectional"))
      (node (ref "MSP1") (pin "60") (pinfunction "P4.4/HSMCLK/SVMHOUT/A9_60") (pintype "power_in"))
    )
    (net (code "99") (name "P4.5_A8_J3.27") (class "Default")
      (node (ref "J3") (pin "27") (pinfunction "7_27") (pintype "bidirectional"))
      (node (ref "MSP1") (pin "61") (pinfunction "P4.5/A8_61") (pintype "power_in"))
    )
    (net (code "100") (name "P4.6_IO_J1.8") (class "Default")
      (node (ref "J1") (pin "8") (pinfunction "8_8") (pintype "bidirectional"))
      (node (ref "MSP1") (pin "62") (pinfunction "P4.6/A7_62") (pintype "power_in"))
    )
    (net (code "101") (name "P4.7_A6_J3.28") (class "Default")
      (node (ref "J3") (pin "28") (pinfunction "8_28") (pintype "bidirectional"))
      (node (ref "MSP1") (pin "63") (pinfunction "P4.7/A6_63") (pintype "power_in"))
    )
    (net (code "102") (name "P5.0_IO_J2.13") (class "Default")
      (node (ref "J2") (pin "13") (pinfunction "8_13") (pintype "bidirectional"))
      (node (ref "MSP1") (pin "64") (pinfunction "P5.0/A5_64") (pintype "power_in"))
    )
    (net (code "103") (name "P5.1_IO_J4.33") (class "Default")
      (node (ref "J4") (pin "33") (pinfunction "8_33") (pintype "bidirectional"))
      (node (ref "MSP1") (pin "65") (pinfunction "P5.1/A4_65") (pintype "power_in"))
    )
    (net (code "104") (name "P5.2_IO_J2.12") (class "Default")
      (node (ref "J2") (pin "12") (pinfunction "9_12") (pintype "bidirectional"))
      (node (ref "MSP1") (pin "66") (pinfunction "P5.2/A3_66") (pintype "power_in"))
    )
    (net (code "105") (name "P5.3") (class "Default")
      (node (ref "J5") (pin "9") (pinfunction "9_9") (pintype "bidirectional"))
      (node (ref "MSP1") (pin "67") (pinfunction "P5.3/A2_67") (pintype "power_in"))
    )
    (net (code "106") (name "P5.4_IO_J3.29") (class "Default")
      (node (ref "J3") (pin "29") (pinfunction "9_29") (pintype "bidirectional"))
      (node (ref "MSP1") (pin "68") (pinfunction "P5.4/A1_68") (pintype "power_in"))
    )
    (net (code "107") (name "P5.5_IO_J3.30") (class "Default")
      (node (ref "J3") (pin "30") (pinfunction "10_30") (pintype "bidirectional"))
      (node (ref "MSP1") (pin "69") (pinfunction "P5.5/A0_69") (pintype "power_in"))
    )
    (net (code "108") (name "P5.6_PWM_J4.37") (class "Default")
      (node (ref "J4") (pin "37") (pinfunction "4_37") (pintype "bidirectional"))
      (node (ref "MSP1") (pin "70") (pinfunction "P5.6/TA2.1/VREF+/VEREF+/C1.7_70") (pintype "power_in"))
    )
    (net (code "109") (name "P5.7_IO_J2.17") (class "Default")
      (node (ref "J2") (pin "17") (pinfunction "4_17") (pintype "bidirectional"))
      (node (ref "MSP1") (pin "71") (pinfunction "P5.7/TA2.2/VREF-/VEREF-/C1.6_71") (pintype "power_in"))
    )
    (net (code "110") (name "P6.0_A15_J1.2") (class "Default")
      (node (ref "J1") (pin "2") (pinfunction "2_2") (pintype "bidirectional"))
      (node (ref "MSP1") (pin "54") (pinfunction "P6.0/A15_54") (pintype "power_in"))
    )
    (net (code "111") (name "P6.1_A14_J3.23") (class "Default")
      (node (ref "J3") (pin "23") (pinfunction "3_23") (pintype "bidirectional"))
      (node (ref "MSP1") (pin "55") (pinfunction "P6.1/A14_55") (pintype "power_in"))
    )
    (net (code "112") (name "P6.2") (class "Default")
      (node (ref "J5") (pin "12") (pinfunction "12_12") (pintype "bidirectional"))
      (node (ref "MSP1") (pin "76") (pinfunction "P6.2/UCB1STE/C1.5_76") (pintype "power_in"))
    )
    (net (code "113") (name "P6.3") (class "Default")
      (node (ref "J5") (pin "13") (pinfunction "13_13") (pintype "bidirectional"))
      (node (ref "MSP1") (pin "77") (pinfunction "P6.3/UCB1CLK/C1.4_77") (pintype "power_in"))
    )
    (net (code "114") (name "P6.4_I2CSDA_J1.10") (class "Default")
      (node (ref "J1") (pin "10") (pinfunction "10_10") (pintype "bidirectional"))
      (node (ref "MSP1") (pin "78") (pinfunction "P6.4/UCB1SIMO/UCB1SDA/C1.3_78") (pintype "power_in"))
    )
    (net (code "115") (name "P6.5_I2CSCL_J1.9") (class "Default")
      (node (ref "J1") (pin "9") (pinfunction "9_9") (pintype "bidirectional"))
      (node (ref "MSP1") (pin "79") (pinfunction "P6.5/UCB1SOMI/UCB1SCL/C1.2_79") (pintype "power_in"))
    )
    (net (code "116") (name "P6.6_CAPTURE_J4.36") (class "Default")
      (node (ref "J4") (pin "36") (pinfunction "5_36") (pintype "bidirectional"))
      (node (ref "MSP1") (pin "80") (pinfunction "P6.6/TA2.3/UCB3SIMO/UCB3SDA/C1.1_80") (pintype "power_in"))
    )
    (net (code "117") (name "P6.7_CAPTURE_J4.35") (class "Default")
      (node (ref "J4") (pin "35") (pinfunction "6_35") (pintype "bidirectional"))
      (node (ref "MSP1") (pin "81") (pinfunction "P6.7/TA2.4/UCB3SOMI/UCB3SCL/C1.0_81") (pintype "power_in"))
    )
    (net (code "118") (name "P7.0") (class "Default")
      (node (ref "J5") (pin "17") (pinfunction "17_17") (pintype "bidirectional"))
      (node (ref "MSP1") (pin "88") (pinfunction "P7.0/PM_SMCLK/PM_DMAE0_88") (pintype "power_in"))
    )
    (net (code "119") (name "P7.1") (class "Default")
      (node (ref "J5") (pin "16") (pinfunction "16_16") (pintype "bidirectional"))
      (node (ref "MSP1") (pin "89") (pinfunction "P7.1/PM_C0OUT/PM_TA0CLK_89") (pintype "power_in"))
    )
    (net (code "120") (name "P7.2") (class "Default")
      (node (ref "J5") (pin "15") (pinfunction "15_15") (pintype "bidirectional"))
      (node (ref "MSP1") (pin "90") (pinfunction "P7.2/PM_C1OUT/PM_TA1CLK_90") (pintype "power_in"))
    )
    (net (code "121") (name "P7.3") (class "Default")
      (node (ref "J5") (pin "14") (pinfunction "14_14") (pintype "bidirectional"))
      (node (ref "MSP1") (pin "91") (pinfunction "P7.3/PM_TA0.0_91") (pintype "power_in"))
    )
    (net (code "122") (name "P7.4") (class "Default")
      (node (ref "J5") (pin "24") (pinfunction "24_24") (pintype "bidirectional"))
      (node (ref "MSP1") (pin "26") (pinfunction "P7.4/PM_TA1.4/C0.5_26") (pintype "power_in"))
    )
    (net (code "123") (name "P7.5") (class "Default")
      (node (ref "J5") (pin "23") (pinfunction "23_23") (pintype "bidirectional"))
      (node (ref "MSP1") (pin "27") (pinfunction "P7.5/PM_TA1.3/C0.4_27") (pintype "power_in"))
    )
    (net (code "124") (name "P7.6") (class "Default")
      (node (ref "J5") (pin "26") (pinfunction "26_26") (pintype "bidirectional"))
      (node (ref "MSP1") (pin "28") (pinfunction "P7.6/PM_TA1.2/C0.3_28") (pintype "power_in"))
    )
    (net (code "125") (name "P7.7") (class "Default")
      (node (ref "J5") (pin "25") (pinfunction "25_25") (pintype "bidirectional"))
      (node (ref "MSP1") (pin "29") (pinfunction "P7.7/PM_TA1.1/C0.2_29") (pintype "power_in"))
    )
    (net (code "126") (name "P8.0") (class "Default")
      (node (ref "J5") (pin "22") (pinfunction "22_22") (pintype "bidirectional"))
      (node (ref "MSP1") (pin "30") (pinfunction "P8.0/UCB3STE/TA1.0/C0.1_30") (pintype "power_in"))
    )
    (net (code "127") (name "P8.1") (class "Default")
      (node (ref "MSP1") (pin "31") (pinfunction "P8.1/UCB3CLK/TA2.0/C0.0_31") (pintype "power_in"))
    )
    (net (code "128") (name "P8.2") (class "Default")
      (node (ref "J5") (pin "8") (pinfunction "8_8") (pintype "bidirectional"))
      (node (ref "MSP1") (pin "46") (pinfunction "P8.2/TA3.2/A23_46") (pintype "power_in"))
    )
    (net (code "129") (name "P8.3") (class "Default")
      (node (ref "J5") (pin "7") (pinfunction "7_7") (pintype "bidirectional"))
      (node (ref "MSP1") (pin "47") (pinfunction "P8.3/TA3CLK/A22_47") (pintype "power_in"))
    )
    (net (code "130") (name "P8.4") (class "Default")
      (node (ref "J5") (pin "6") (pinfunction "6_6") (pintype "bidirectional"))
      (node (ref "MSP1") (pin "48") (pinfunction "P8.4/A21_48") (pintype "power_in"))
    )
    (net (code "131") (name "P8.5") (class "Default")
      (node (ref "J5") (pin "2") (pinfunction "2_2") (pintype "bidirectional"))
      (node (ref "MSP1") (pin "49") (pinfunction "P8.5/A20_49") (pintype "power_in"))
    )
    (net (code "132") (name "P8.6") (class "Default")
      (node (ref "J5") (pin "1") (pinfunction "1_1") (pintype "bidirectional"))
      (node (ref "MSP1") (pin "50") (pinfunction "P8.6/A19_50") (pintype "power_in"))
    )
    (net (code "133") (name "P8.7") (class "Default")
      (node (ref "J5") (pin "3") (pinfunction "3_3") (pintype "bidirectional"))
      (node (ref "MSP1") (pin "51") (pinfunction "P8.7/A18_51") (pintype "power_in"))
    )
    (net (code "134") (name "P9.0") (class "Default")
      (node (ref "J5") (pin "4") (pinfunction "4_4") (pintype "bidirectional"))
      (node (ref "MSP1") (pin "52") (pinfunction "P9.0/A17_52") (pintype "power_in"))
    )
    (net (code "135") (name "P9.1") (class "Default")
      (node (ref "J5") (pin "5") (pinfunction "5_5") (pintype "bidirectional"))
      (node (ref "MSP1") (pin "53") (pinfunction "P9.1/A16_53") (pintype "power_in"))
    )
    (net (code "136") (name "P9.2") (class "Default")
      (node (ref "J5") (pin "10") (pinfunction "10_10") (pintype "bidirectional"))
      (node (ref "MSP1") (pin "74") (pinfunction "P9.2/TA3.3_74") (pintype "power_in"))
    )
    (net (code "137") (name "P9.3") (class "Default")
      (node (ref "J5") (pin "11") (pinfunction "11_11") (pintype "bidirectional"))
      (node (ref "MSP1") (pin "75") (pinfunction "P9.3/TA3.4_75") (pintype "power_in"))
    )
    (net (code "138") (name "P9.4") (class "Default")
      (node (ref "J5") (pin "18") (pinfunction "18_18") (pintype "bidirectional"))
      (node (ref "MSP1") (pin "96") (pinfunction "P9.4/UCA3STE_96") (pintype "power_in"))
    )
    (net (code "139") (name "P9.5") (class "Default")
      (node (ref "J5") (pin "19") (pinfunction "19_19") (pintype "bidirectional"))
      (node (ref "MSP1") (pin "97") (pinfunction "P9.5/UCA3CLK_97") (pintype "power_in"))
    )
    (net (code "140") (name "P9.6") (class "Default")
      (node (ref "J5") (pin "20") (pinfunction "20_20") (pintype "bidirectional"))
      (node (ref "MSP1") (pin "98") (pinfunction "P9.6/UCA3RXD/UCA3SOMI_98") (pintype "power_in"))
    )
    (net (code "141") (name "P9.7") (class "Default")
      (node (ref "J5") (pin "21") (pinfunction "21_21") (pintype "bidirectional"))
      (node (ref "MSP1") (pin "99") (pinfunction "P9.7/UCA3TXD/UCA3SIMO_99") (pintype "power_in"))
    )
    (net (code "142") (name "P10.0") (class "Default")
      (node (ref "J5") (pin "28") (pinfunction "28_28") (pintype "bidirectional"))
      (node (ref "MSP1") (pin "100") (pinfunction "P10.0/UCB3STE_100") (pintype "power_in"))
    )
    (net (code "143") (name "P10.1") (class "Default")
      (node (ref "J5") (pin "27") (pinfunction "27_27") (pintype "bidirectional"))
      (node (ref "MSP1") (pin "1") (pinfunction "P10.1/UCB3CLK_1") (pintype "power_in"))
    )
    (net (code "144") (name "P10.2") (class "Default")
      (node (ref "J5") (pin "30") (pinfunction "30_30") (pintype "bidirectional"))
      (node (ref "MSP1") (pin "2") (pinfunction "P10.2/UCB3SIMO/UCB3SDA_2") (pintype "power_in"))
    )
    (net (code "145") (name "P10.3") (class "Default")
      (node (ref "J5") (pin "29") (pinfunction "29_29") (pintype "bidirectional"))
      (node (ref "MSP1") (pin "3") (pinfunction "P10.3UCB3SOMI/UCB3SCL_3") (pintype "power_in"))
    )
    (net (code "146") (name "P10.4") (class "Default")
      (node (ref "J5") (pin "32") (pinfunction "32_32") (pintype "bidirectional"))
      (node (ref "MSP1") (pin "24") (pinfunction "P10.4/TA3.0/C0.7_24") (pintype "power_in"))
    )
    (net (code "147") (name "P10.5") (class "Default")
      (node (ref "J5") (pin "31") (pinfunction "31_31") (pintype "bidirectional"))
      (node (ref "MSP1") (pin "25") (pinfunction "P10.5/TA3.1/C0.6_25") (pintype "power_in"))
    )
    (net (code "148") (name "REF_MAIN_LDO") (class "Default")
      (node (ref "IC106") (pin "P$128") (pinfunction "PD7_P$128") (pintype "bidirectional"))
      (node (ref "R135") (pin "2") (pinfunction "2_2") (pintype "passive"))
      (node (ref "R136") (pin "2") (pinfunction "2_2") (pintype "passive"))
    )
    (net (code "149") (name "REF_TARGET_VCC") (class "Default")
      (node (ref "IC106") (pin "P$120") (pinfunction "PB5_P$120") (pintype "bidirectional"))
      (node (ref "R101") (pin "2") (pinfunction "2_2") (pintype "passive"))
      (node (ref "R134") (pin "2") (pinfunction "2_2") (pintype "passive"))
    )
    (net (code "150") (name "TCK_SWCLK") (class "Default")
      (node (ref "IC111") (pin "5") (pinfunction "2A_5") (pintype "bidirectional"))
      (node (ref "MSP1") (pin "95") (pinfunction "SWCLKTCK_95") (pintype "power_in"))
    )
    (net (code "151") (name "TDI") (class "Default")
      (node (ref "MSP1") (pin "92") (pinfunction "PJ.4/TDI/ADC14CLK_92") (pintype "power_in"))
      (node (ref "S101") (pin "5") (pinfunction "C2_5") (pintype "bidirectional"))
    )
    (net (code "152") (name "TDO_SWO") (class "Default")
      (node (ref "IC111") (pin "10") (pinfunction "4A_10") (pintype "bidirectional"))
      (node (ref "MSP1") (pin "93") (pinfunction "PJ.5/TDO/SWO_93") (pintype "power_in"))
    )
    (net (code "153") (name "TMS_SWDIO") (class "Default")
      (node (ref "IC111") (pin "2") (pinfunction "1A_2") (pintype "bidirectional"))
      (node (ref "MSP1") (pin "94") (pinfunction "SWDIOTMS_94") (pintype "power_in"))
    )
    (net (code "154") (name "USB0CLK") (class "Default")
      (node (ref "IC106") (pin "P$92") (pinfunction "PB3_P$92") (pintype "bidirectional"))
      (node (ref "IC110") (pin "12") (pinfunction "2B2_12") (pintype "bidirectional"))
    )
    (net (code "155") (name "USB0CLK_18") (class "Default")
      (node (ref "IC105") (pin "26") (pinfunction "CLOCK_26") (pintype "output"))
      (node (ref "IC110") (pin "9") (pinfunction "2A2_9") (pintype "bidirectional"))
    )
    (net (code "156") (name "USB0D0") (class "Default")
      (node (ref "IC106") (pin "P$81") (pinfunction "PL0_P$81") (pintype "bidirectional"))
      (node (ref "IC108") (pin "15") (pinfunction "1B1_15") (pintype "bidirectional"))
    )
    (net (code "157") (name "USB0D0_18") (class "Default")
      (node (ref "IC105") (pin "3") (pinfunction "DATA0_3") (pintype "bidirectional"))
      (node (ref "IC108") (pin "6") (pinfunction "1A1_6") (pintype "bidirectional"))
    )
    (net (code "158") (name "USB0D1") (class "Default")
      (node (ref "IC106") (pin "P$82") (pinfunction "PL1_P$82") (pintype "bidirectional"))
      (node (ref "IC108") (pin "14") (pinfunction "1B2_14") (pintype "bidirectional"))
    )
    (net (code "159") (name "USB0D1_18") (class "Default")
      (node (ref "IC105") (pin "4") (pinfunction "DATA1_4") (pintype "bidirectional"))
      (node (ref "IC108") (pin "7") (pinfunction "1A2_7") (pintype "bidirectional"))
    )
    (net (code "160") (name "USB0D2") (class "Default")
      (node (ref "IC106") (pin "P$83") (pinfunction "PL2_P$83") (pintype "bidirectional"))
      (node (ref "IC108") (pin "13") (pinfunction "2B1_13") (pintype "bidirectional"))
    )
    (net (code "161") (name "USB0D2_18") (class "Default")
      (node (ref "IC105") (pin "5") (pinfunction "DATA2_5") (pintype "bidirectional"))
      (node (ref "IC108") (pin "8") (pinfunction "2A1_8") (pintype "bidirectional"))
    )
    (net (code "162") (name "USB0D3") (class "Default")
      (node (ref "IC106") (pin "P$84") (pinfunction "PL3_P$84") (pintype "bidirectional"))
      (node (ref "IC108") (pin "12") (pinfunction "2B2_12") (pintype "bidirectional"))
    )
    (net (code "163") (name "USB0D3_18") (class "Default")
      (node (ref "IC105") (pin "6") (pinfunction "DATA3_6") (pintype "bidirectional"))
      (node (ref "IC108") (pin "9") (pinfunction "2A2_9") (pintype "bidirectional"))
    )
    (net (code "164") (name "USB0D4") (class "Default")
      (node (ref "IC106") (pin "P$85") (pinfunction "PL4_P$85") (pintype "bidirectional"))
      (node (ref "IC109") (pin "15") (pinfunction "1B1_15") (pintype "bidirectional"))
    )
    (net (code "165") (name "USB0D4_18") (class "Default")
      (node (ref "IC105") (pin "7") (pinfunction "DATA4_7") (pintype "bidirectional"))
      (node (ref "IC109") (pin "6") (pinfunction "1A1_6") (pintype "bidirectional"))
    )
    (net (code "166") (name "USB0D5") (class "Default")
      (node (ref "IC106") (pin "P$86") (pinfunction "PL5_P$86") (pintype "bidirectional"))
      (node (ref "IC109") (pin "14") (pinfunction "1B2_14") (pintype "bidirectional"))
    )
    (net (code "167") (name "USB0D5_18") (class "Default")
      (node (ref "IC105") (pin "9") (pinfunction "DATA5_9") (pintype "bidirectional"))
      (node (ref "IC109") (pin "7") (pinfunction "1A2_7") (pintype "bidirectional"))
    )
    (net (code "168") (name "USB0D6") (class "Default")
      (node (ref "IC106") (pin "P$106") (pinfunction "PP5_P$106") (pintype "bidirectional"))
      (node (ref "IC109") (pin "13") (pinfunction "2B1_13") (pintype "bidirectional"))
    )
    (net (code "169") (name "USB0D6_18") (class "Default")
      (node (ref "IC105") (pin "10") (pinfunction "DATA6_10") (pintype "bidirectional"))
      (node (ref "IC109") (pin "8") (pinfunction "2A1_8") (pintype "bidirectional"))
    )
    (net (code "170") (name "USB0D7") (class "Default")
      (node (ref "IC106") (pin "P$105") (pinfunction "PP4_P$105") (pintype "bidirectional"))
      (node (ref "IC109") (pin "12") (pinfunction "2B2_12") (pintype "bidirectional"))
    )
    (net (code "171") (name "USB0D7_18") (class "Default")
      (node (ref "IC105") (pin "13") (pinfunction "DATA7_13") (pintype "bidirectional"))
      (node (ref "IC109") (pin "9") (pinfunction "2A2_9") (pintype "bidirectional"))
    )
    (net (code "172") (name "USBDIR") (class "Default")
      (node (ref "IC106") (pin "P$104") (pinfunction "PP3_P$104") (pintype "bidirectional"))
      (node (ref "IC110") (pin "15") (pinfunction "1B1_15") (pintype "bidirectional"))
    )
    (net (code "173") (name "USBDIR_HS") (class "Default")
      (node (ref "IC105") (pin "31") (pinfunction "DIR_31") (pintype "output"))
      (node (ref "IC108") (pin "4") (pinfunction "1DIR_4") (pintype "input"))
      (node (ref "IC108") (pin "5") (pinfunction "2DIR_5") (pintype "input"))
      (node (ref "IC109") (pin "4") (pinfunction "1DIR_4") (pintype "input"))
      (node (ref "IC109") (pin "5") (pinfunction "2DIR_5") (pintype "input"))
      (node (ref "IC110") (pin "6") (pinfunction "1A1_6") (pintype "bidirectional"))
    )
    (net (code "174") (name "USBNXT") (class "Default")
      (node (ref "IC106") (pin "P$103") (pinfunction "PP2_P$103") (pintype "bidirectional"))
      (node (ref "IC110") (pin "14") (pinfunction "1B2_14") (pintype "bidirectional"))
    )
    (net (code "175") (name "USBNXT_18") (class "Default")
      (node (ref "IC105") (pin "2") (pinfunction "NXT_2") (pintype "output"))
      (node (ref "IC110") (pin "7") (pinfunction "1A2_7") (pintype "bidirectional"))
    )
    (net (code "176") (name "USBSTP") (class "Default")
      (node (ref "IC106") (pin "P$91") (pinfunction "PB2_P$91") (pintype "bidirectional"))
      (node (ref "IC110") (pin "13") (pinfunction "2B1_13") (pintype "bidirectional"))
    )
    (net (code "177") (name "USBSTP_18") (class "Default")
      (node (ref "IC105") (pin "29") (pinfunction "STP_29") (pintype "input"))
      (node (ref "IC110") (pin "8") (pinfunction "2A1_8") (pintype "bidirectional"))
    )
    (net (code "178") (name "VBUS_DETECT") (class "Default")
      (node (ref "IC106") (pin "P$1") (pinfunction "PD0_P$1") (pintype "bidirectional"))
      (node (ref "R132") (pin "2") (pinfunction "2_2") (pintype "passive"))
      (node (ref "R133") (pin "2") (pinfunction "2_2") (pintype "passive"))
    )
    (net (code "179") (name "VCCEN1") (class "Default")
      (node (ref "IC103") (pin "1") (pinfunction "~{EN}_1") (pintype "bidirectional"))
      (node (ref "IC106") (pin "P$78") (pinfunction "PM0_P$78") (pintype "bidirectional"))
      (node (ref "R107") (pin "1") (pinfunction "1_1") (pintype "passive"))
      (node (ref "TP110") (pin "1") (pinfunction "1_1") (pintype "passive"))
    )
    (net (code "180") (name "VCCEN2") (class "Default")
      (node (ref "IC106") (pin "P$77") (pinfunction "PM1_P$77") (pintype "bidirectional"))
    )
    (net (code "181") (name "VCORE") (class "Default")
      (node (ref "C10") (pin "1") (pinfunction "1_1") (pintype "passive"))
      (node (ref "C8") (pin "1") (pinfunction "1_1") (pintype "passive"))
      (node (ref "L1") (pin "1") (pinfunction "1_1") (pintype "passive"))
      (node (ref "MSP1") (pin "12") (pinfunction "VCORE_12") (pintype "power_in"))
    )
    (net (code "182") (name "VDDC") (class "Default")
      (node (ref "C131") (pin "1") (pinfunction "1_1") (pintype "passive"))
      (node (ref "C132") (pin "2") (pinfunction "2_2") (pintype "passive"))
      (node (ref "C133") (pin "1") (pinfunction "1_1") (pintype "passive"))
      (node (ref "IC106") (pin "P$115") (pinfunction "VDDC_P$115") (pintype "bidirectional"))
      (node (ref "IC106") (pin "P$87") (pinfunction "VDDC_P$87") (pintype "bidirectional"))
    )
    (net (code "183") (name "VREFA+") (class "Default")
      (node (ref "C110") (pin "1") (pinfunction "1_1") (pintype "passive"))
      (node (ref "C111") (pin "1") (pinfunction "1_1") (pintype "passive"))
      (node (ref "IC106") (pin "P$9") (pinfunction "VREFA+_P$9") (pintype "bidirectional"))
      (node (ref "IC107") (pin "3") (pinfunction "C_3") (pintype "passive"))
      (node (ref "R105") (pin "1") (pinfunction "1_1") (pintype "passive"))
    )
    (net (code "184") (name "VSW") (class "Default")
      (node (ref "L1") (pin "2") (pinfunction "2_2") (pintype "passive"))
      (node (ref "MSP1") (pin "14") (pinfunction "VSW_14") (pintype "power_in"))
    )
    (net (code "185") (name "XDSET_1V8") (class "Default")
      (node (ref "C109") (pin "1") (pinfunction "1_1") (pintype "passive"))
      (node (ref "C135") (pin "1") (pinfunction "1_1") (pintype "passive"))
      (node (ref "C143") (pin "1") (pinfunction "1_1") (pintype "passive"))
      (node (ref "C144") (pin "1") (pinfunction "1_1") (pintype "passive"))
      (node (ref "C145") (pin "1") (pinfunction "1_1") (pintype "passive"))
      (node (ref "C147") (pin "1") (pinfunction "1_1") (pintype "passive"))
      (node (ref "IC104") (pin "3") (pinfunction "OUT_3") (pintype "output"))
      (node (ref "IC105") (pin "30") (pinfunction "VDD18_30") (pintype "power_in"))
      (node (ref "IC108") (pin "3") (pinfunction "VCCA_3") (pintype "power_in"))
      (node (ref "IC109") (pin "3") (pinfunction "VCCA_3") (pintype "power_in"))
      (node (ref "IC110") (pin "3") (pinfunction "VCCA_3") (pintype "power_in"))
      (node (ref "IC110") (pin "4") (pinfunction "1DIR_4") (pintype "input"))
    )
    (net (code "186") (name "XDSET_CTS") (class "Default")
      (node (ref "IC106") (pin "P$30") (pinfunction "PH1_P$30") (pintype "bidirectional"))
      (node (ref "JP4.1") (pin "1") (pinfunction "1_1") (pintype "passive"))
    )
    (net (code "187") (name "XDSET_DM") (class "Default")
      (node (ref "IC102") (pin "4") (pinfunction "IO3_4") (pintype "passive"))
      (node (ref "J101") (pin "D-") (pinfunction "D-_D-") (pintype "input"))
      (node (ref "R122") (pin "2") (pinfunction "2_2") (pintype "passive"))
      (node (ref "R138") (pin "1") (pinfunction "1_1") (pintype "passive"))
    )
    (net (code "188") (name "XDSET_DP") (class "Default")
      (node (ref "IC102") (pin "1") (pinfunction "IO1_1") (pintype "passive"))
      (node (ref "J101") (pin "D+") (pinfunction "D+_D+") (pintype "input"))
      (node (ref "R121") (pin "2") (pinfunction "2_2") (pintype "passive"))
      (node (ref "R137") (pin "1") (pinfunction "1_1") (pintype "passive"))
    )
    (net (code "189") (name "XDSET_ID") (class "Default")
      (node (ref "IC102") (pin "2") (pinfunction "IO2_2") (pintype "passive"))
      (node (ref "J101") (pin "NC") (pinfunction "NC_NC") (pintype "input"))
      (node (ref "R130") (pin "1") (pinfunction "1_1") (pintype "passive"))
      (node (ref "R131") (pin "1") (pinfunction "1_1") (pintype "passive"))
    )
    (net (code "190") (name "XDSET_RESET_OUT") (class "Default")
      (node (ref "IC106") (pin "P$40") (pinfunction "PA6_P$40") (pintype "bidirectional"))
      (node (ref "IC111") (pin "9") (pinfunction "3B1_9") (pintype "bidirectional"))
      (node (ref "J103") (pin "4") (pinfunction "4_4") (pintype "passive"))
    )
    (net (code "191") (name "XDSET_RTS") (class "Default")
      (node (ref "IC106") (pin "P$29") (pinfunction "PH0_P$29") (pintype "bidirectional"))
      (node (ref "JP4.2") (pin "1") (pinfunction "1_1") (pintype "passive"))
    )
    (net (code "192") (name "XDSET_RXD") (class "Default")
      (node (ref "IC106") (pin "P$33") (pinfunction "PA0_P$33") (pintype "bidirectional"))
      (node (ref "J103") (pin "6") (pinfunction "6_6") (pintype "passive"))
      (node (ref "JP4.4") (pin "1") (pinfunction "1_1") (pintype "passive"))
    )
    (net (code "193") (name "XDSET_SHIELD") (class "Default")
      (node (ref "IC102") (pin "5") (pinfunction "IO4_5") (pintype "passive"))
      (node (ref "J101") (pin "SHIELD3") (pinfunction "SHIELD3_SHIELD3") (pintype "bidirectional"))
      (node (ref "R123") (pin "1") (pinfunction "1_1") (pintype "passive"))
    )
    (net (code "194") (name "XDSET_TCK_SWCLK") (class "Default")
      (node (ref "IC106") (pin "P$35") (pinfunction "PA2_P$35") (pintype "bidirectional"))
      (node (ref "IC111") (pin "3") (pinfunction "2B1_3") (pintype "bidirectional"))
      (node (ref "J103") (pin "3") (pinfunction "3_3") (pintype "passive"))
    )
    (net (code "195") (name "XDSET_TDI") (class "Default")
      (node (ref "IC106") (pin "P$38") (pinfunction "PA5_P$38") (pintype "bidirectional"))
      (node (ref "S101") (pin "6") (pinfunction "L4_6") (pintype "bidirectional"))
    )
    (net (code "196") (name "XDSET_TDO_SWO") (class "Default")
      (node (ref "IC106") (pin "P$37") (pinfunction "PA4_P$37") (pintype "bidirectional"))
      (node (ref "IC111") (pin "12") (pinfunction "4B1_12") (pintype "bidirectional"))
    )
    (net (code "197") (name "XDSET_TMS_SWDIO") (class "Default")
      (node (ref "IC106") (pin "P$36") (pinfunction "PA3_P$36") (pintype "bidirectional"))
      (node (ref "IC111") (pin "16") (pinfunction "1B1_16") (pintype "bidirectional"))
      (node (ref "J103") (pin "2") (pinfunction "2_2") (pintype "passive"))
    )
    (net (code "198") (name "XDSET_TXD") (class "Default")
      (node (ref "IC106") (pin "P$34") (pinfunction "PA1_P$34") (pintype "bidirectional"))
      (node (ref "J103") (pin "5") (pinfunction "5_5") (pintype "passive"))
      (node (ref "JP4.3") (pin "1") (pinfunction "1_1") (pintype "passive"))
    )
    (net (code "199") (name "XDSET_VBAT") (class "Default")
      (node (ref "C103") (pin "1") (pinfunction "1_1") (pintype "passive"))
      (node (ref "IC106") (pin "P$68") (pinfunction "VBAT_P$68") (pintype "bidirectional"))
      (node (ref "R104") (pin "2") (pinfunction "2_2") (pintype "passive"))
    )
    (net (code "200") (name "XDSET_VBUS") (class "Default")
      (node (ref "C117") (pin "1") (pinfunction "1_1") (pintype "passive"))
      (node (ref "C118") (pin "1") (pinfunction "1_1") (pintype "passive"))
      (node (ref "C140") (pin "+") (pinfunction "+_+") (pintype "passive"))
      (node (ref "C141") (pin "1") (pinfunction "1_1") (pintype "passive"))
      (node (ref "C142") (pin "1") (pinfunction "1_1") (pintype "passive"))
      (node (ref "IC101") (pin "5") (pinfunction "EN_5") (pintype "bidirectional"))
      (node (ref "IC101") (pin "8") (pinfunction "IN_8") (pintype "bidirectional"))
      (node (ref "IC102") (pin "6") (pinfunction "VCC_6") (pintype "power_in"))
      (node (ref "IC104") (pin "1") (pinfunction "IN_1") (pintype "input"))
      (node (ref "IC104") (pin "6") (pinfunction "EN_6") (pintype "passive"))
      (node (ref "IC105") (pin "22") (pinfunction "VBUS_22") (pintype "power_in"))
      (node (ref "IC106") (pin "P$96") (pinfunction "PB1_P$96") (pintype "bidirectional"))
      (node (ref "J101") (pin "VBUS") (pinfunction "VBUS_VBUS") (pintype "input"))
      (node (ref "JP2") (pin "1") (pinfunction "1_1") (pintype "passive"))
      (node (ref "R120") (pin "1") (pinfunction "1_1") (pintype "passive"))
      (node (ref "R132") (pin "1") (pinfunction "1_1") (pintype "passive"))
      (node (ref "T101") (pin "2") (pinfunction "S_2") (pintype "passive"))
    )
    (net (code "201") (name "XDSET_VCC") (class "Default")
      (node (ref "C104") (pin "1") (pinfunction "1_1") (pintype "passive"))
      (node (ref "C105") (pin "1") (pinfunction "1_1") (pintype "passive"))
      (node (ref "C106") (pin "+") (pinfunction "+_+") (pintype "passive"))
      (node (ref "C107") (pin "1") (pinfunction "1_1") (pintype "passive"))
      (node (ref "C112") (pin "1") (pinfunction "1_1") (pintype "passive"))
      (node (ref "C113") (pin "1") (pinfunction "1_1") (pintype "passive"))
      (node (ref "C114") (pin "1") (pinfunction "1_1") (pintype "passive"))
      (node (ref "C121") (pin "1") (pinfunction "1_1") (pintype "passive"))
      (node (ref "C122") (pin "1") (pinfunction "1_1") (pintype "passive"))
      (node (ref "C123") (pin "1") (pinfunction "1_1") (pintype "passive"))
      (node (ref "C124") (pin "1") (pinfunction "1_1") (pintype "passive"))
      (node (ref "C126") (pin "1") (pinfunction "1_1") (pintype "passive"))
      (node (ref "C130") (pin "2") (pinfunction "2_2") (pintype "passive"))
      (node (ref "C136") (pin "1") (pinfunction "1_1") (pintype "passive"))
      (node (ref "C138") (pin "1") (pinfunction "1_1") (pintype "passive"))
      (node (ref "C146") (pin "1") (pinfunction "1_1") (pintype "passive"))
      (node (ref "C148") (pin "1") (pinfunction "1_1") (pintype "passive"))
      (node (ref "C149") (pin "1") (pinfunction "1_1") (pintype "passive"))
      (node (ref "IC101") (pin "1") (pinfunction "OUT_1") (pintype "bidirectional"))
      (node (ref "IC103") (pin "5") (pinfunction "IN1_5") (pintype "bidirectional"))
      (node (ref "IC105") (pin "11") (pinfunction "CS_11") (pintype "input"))
      (node (ref "IC105") (pin "14") (pinfunction "CFG_14") (pintype "input"))
      (node (ref "IC105") (pin "21") (pinfunction "VBAT_21") (pintype "power_in"))
      (node (ref "IC105") (pin "27") (pinfunction "RESETB_27") (pintype "input"))
      (node (ref "IC105") (pin "32") (pinfunction "VDDIO_32") (pintype "power_in"))
      (node (ref "IC106") (pin "P$101") (pinfunction "VDD_P$101") (pintype "bidirectional"))
      (node (ref "IC106") (pin "P$113") (pinfunction "VDD_P$113") (pintype "bidirectional"))
      (node (ref "IC106") (pin "P$122") (pinfunction "VDD_P$122") (pintype "bidirectional"))
      (node (ref "IC106") (pin "P$16") (pinfunction "VDD_P$16") (pintype "bidirectional"))
      (node (ref "IC106") (pin "P$26") (pinfunction "VDD_P$26") (pintype "bidirectional"))
      (node (ref "IC106") (pin "P$28") (pinfunction "VDD_P$28") (pintype "bidirectional"))
      (node (ref "IC106") (pin "P$39") (pinfunction "VDD_P$39") (pintype "bidirectional"))
      (node (ref "IC106") (pin "P$47") (pinfunction "VDD_P$47") (pintype "bidirectional"))
      (node (ref "IC106") (pin "P$51") (pinfunction "VDD_P$51") (pintype "bidirectional"))
      (node (ref "IC106") (pin "P$52") (pinfunction "VDD_P$52") (pintype "bidirectional"))
      (node (ref "IC106") (pin "P$69") (pinfunction "VDD_P$69") (pintype "bidirectional"))
      (node (ref "IC106") (pin "P$7") (pinfunction "VDD_P$7") (pintype "bidirectional"))
      (node (ref "IC106") (pin "P$79") (pinfunction "VDD_P$79") (pintype "bidirectional"))
      (node (ref "IC106") (pin "P$8") (pinfunction "VDDA_P$8") (pintype "bidirectional"))
      (node (ref "IC106") (pin "P$90") (pinfunction "VDD_P$90") (pintype "bidirectional"))
      (node (ref "IC108") (pin "2") (pinfunction "VCCB_2") (pintype "power_in"))
      (node (ref "IC109") (pin "2") (pinfunction "VCCB_2") (pintype "power_in"))
      (node (ref "IC110") (pin "2") (pinfunction "VCCB_2") (pintype "power_in"))
      (node (ref "IC111") (pin "14") (pinfunction "VCC_14") (pintype "bidirectional"))
      (node (ref "MSP101") (pin "15") (pinfunction "15_15") (pintype "bidirectional"))
      (node (ref "MSP101") (pin "16") (pinfunction "16_16") (pintype "bidirectional"))
      (node (ref "R103") (pin "1") (pinfunction "1_1") (pintype "passive"))
      (node (ref "R104") (pin "1") (pinfunction "1_1") (pintype "passive"))
      (node (ref "R105") (pin "2") (pinfunction "2_2") (pintype "passive"))
      (node (ref "R114") (pin "1") (pinfunction "1_1") (pintype "passive"))
      (node (ref "R116") (pin "1") (pinfunction "1_1") (pintype "passive"))
      (node (ref "R117") (pin "1") (pinfunction "1_1") (pintype "passive"))
      (node (ref "R125") (pin "2") (pinfunction "2_2") (pintype "passive"))
      (node (ref "R129") (pin "2") (pinfunction "2_2") (pintype "passive"))
      (node (ref "R135") (pin "1") (pinfunction "1_1") (pintype "passive"))
      (node (ref "S101") (pin "1") (pinfunction "L1_1") (pintype "bidirectional"))
      (node (ref "TP107") (pin "1") (pinfunction "1_1") (pintype "passive"))
    )
    (net (code "202") (name "XDSET_VCCOUT") (class "Default")
      (node (ref "C119") (pin "1") (pinfunction "1_1") (pintype "passive"))
      (node (ref "C120") (pin "1") (pinfunction "1_1") (pintype "passive"))
      (node (ref "C127") (pin "1") (pinfunction "1_1") (pintype "passive"))
      (node (ref "IC103") (pin "3") (pinfunction "IN2_3") (pintype "bidirectional"))
      (node (ref "L101") (pin "2") (pinfunction "2_2") (pintype "passive"))
      (node (ref "R112") (pin "1") (pinfunction "1_1") (pintype "passive"))
      (node (ref "R126") (pin "1") (pinfunction "1_1") (pintype "passive"))
      (node (ref "R127") (pin "1") (pinfunction "1_1") (pintype "passive"))
      (node (ref "R128") (pin "1") (pinfunction "1_1") (pintype "passive"))
    )
    (net (code "203") (name "XDSET_VCCTARGET") (class "Default")
      (node (ref "C128") (pin "+") (pinfunction "+_+") (pintype "passive"))
      (node (ref "C129") (pin "1") (pinfunction "1_1") (pintype "passive"))
      (node (ref "IC103") (pin "4") (pinfunction "OUT_4") (pintype "bidirectional"))
      (node (ref "J103") (pin "1") (pinfunction "1_1") (pintype "passive"))
      (node (ref "JP3") (pin "1") (pinfunction "1_1") (pintype "passive"))
      (node (ref "R134") (pin "1") (pinfunction "1_1") (pintype "passive"))
    )
    (net (code "204") (name "XDSET_~{RST}") (class "Default")
      (node (ref "C108") (pin "1") (pinfunction "1_1") (pintype "passive"))
      (node (ref "IC106") (pin "P$70") (pinfunction "~{RESET}_P$70") (pintype "bidirectional"))
      (node (ref "R102") (pin "2") (pinfunction "2_2") (pintype "passive"))
      (node (ref "R103") (pin "2") (pinfunction "2_2") (pintype "passive"))
    )
    (net (code "205") (name "unconnected-(IC101-NC0-Pad2)") (class "Default")
      (node (ref "IC101") (pin "2") (pinfunction "NC0_2") (pintype "bidirectional"))
    )
    (net (code "206") (name "unconnected-(IC101-NC1-Pad6)") (class "Default")
      (node (ref "IC101") (pin "6") (pinfunction "NC1_6") (pintype "bidirectional"))
    )
    (net (code "207") (name "unconnected-(IC101-NC2-Pad7)") (class "Default")
      (node (ref "IC101") (pin "7") (pinfunction "NC2_7") (pintype "bidirectional"))
    )
    (net (code "208") (name "unconnected-(IC104-NC-Pad5)") (class "Default")
      (node (ref "IC104") (pin "5") (pinfunction "NC_5") (pintype "passive"))
    )
    (net (code "209") (name "unconnected-(IC104-NC_2-Pad4)") (class "Default")
      (node (ref "IC104") (pin "4") (pinfunction "NC_2_4") (pintype "passive"))
    )
    (net (code "210") (name "unconnected-(IC105-CPEN-Pad17)") (class "Default")
      (node (ref "IC105") (pin "17") (pinfunction "CPEN_17") (pintype "output"))
    )
    (net (code "211") (name "unconnected-(IC105-NC-Pad25)") (class "Default")
      (node (ref "IC105") (pin "25") (pinfunction "NC_25") (pintype "passive"))
    )
    (net (code "212") (name "unconnected-(IC105-NC_2-Pad8)") (class "Default")
      (node (ref "IC105") (pin "8") (pinfunction "NC_2_8") (pintype "passive"))
    )
    (net (code "213") (name "unconnected-(IC105-NC_3-Pad15)") (class "Default")
      (node (ref "IC105") (pin "15") (pinfunction "NC_3_15") (pintype "passive"))
    )
    (net (code "214") (name "unconnected-(IC105-NC_4-Pad16)") (class "Default")
      (node (ref "IC105") (pin "16") (pinfunction "NC_4_16") (pintype "passive"))
    )
    (net (code "215") (name "unconnected-(IC105-NC_5-Pad24)") (class "Default")
      (node (ref "IC105") (pin "24") (pinfunction "NC_5_24") (pintype "passive"))
    )
    (net (code "216") (name "unconnected-(IC106A-PB4-PadP$121)") (class "Default")
      (node (ref "IC106") (pin "P$121") (pinfunction "PB4_P$121") (pintype "bidirectional"))
    )
    (net (code "217") (name "unconnected-(IC106A-PC4-PadP$25)") (class "Default")
      (node (ref "IC106") (pin "P$25") (pinfunction "PC4_P$25") (pintype "bidirectional"))
    )
    (net (code "218") (name "unconnected-(IC106A-PC5-PadP$24)") (class "Default")
      (node (ref "IC106") (pin "P$24") (pinfunction "PC5_P$24") (pintype "bidirectional"))
    )
    (net (code "219") (name "unconnected-(IC106A-PC6-PadP$23)") (class "Default")
      (node (ref "IC106") (pin "P$23") (pinfunction "PC6_P$23") (pintype "bidirectional"))
    )
    (net (code "220") (name "unconnected-(IC106A-PC7-PadP$22)") (class "Default")
      (node (ref "IC106") (pin "P$22") (pinfunction "PC7_P$22") (pintype "bidirectional"))
    )
    (net (code "221") (name "unconnected-(IC106A-PD1-PadP$2)") (class "Default")
      (node (ref "IC106") (pin "P$2") (pinfunction "PD1_P$2") (pintype "bidirectional"))
    )
    (net (code "222") (name "unconnected-(IC106A-PD4-PadP$125)") (class "Default")
      (node (ref "IC106") (pin "P$125") (pinfunction "PD4_P$125") (pintype "bidirectional"))
    )
    (net (code "223") (name "unconnected-(IC106A-PD5-PadP$126)") (class "Default")
      (node (ref "IC106") (pin "P$126") (pinfunction "PD5_P$126") (pintype "bidirectional"))
    )
    (net (code "224") (name "unconnected-(IC106A-PE0-PadP$15)") (class "Default")
      (node (ref "IC106") (pin "P$15") (pinfunction "PE0_P$15") (pintype "bidirectional"))
    )
    (net (code "225") (name "unconnected-(IC106A-PE1-PadP$14)") (class "Default")
      (node (ref "IC106") (pin "P$14") (pinfunction "PE1_P$14") (pintype "bidirectional"))
    )
    (net (code "226") (name "unconnected-(IC106A-PE2-PadP$13)") (class "Default")
      (node (ref "IC106") (pin "P$13") (pinfunction "PE2_P$13") (pintype "bidirectional"))
    )
    (net (code "227") (name "unconnected-(IC106A-PE3-PadP$12)") (class "Default")
      (node (ref "IC106") (pin "P$12") (pinfunction "PE3_P$12") (pintype "bidirectional"))
    )
    (net (code "228") (name "unconnected-(IC106A-PE4-PadP$123)") (class "Default")
      (node (ref "IC106") (pin "P$123") (pinfunction "PE4_P$123") (pintype "bidirectional"))
    )
    (net (code "229") (name "unconnected-(IC106A-PE5-PadP$124)") (class "Default")
      (node (ref "IC106") (pin "P$124") (pinfunction "PE5_P$124") (pintype "bidirectional"))
    )
    (net (code "230") (name "unconnected-(IC106A-PF0-PadP$42)") (class "Default")
      (node (ref "IC106") (pin "P$42") (pinfunction "PF0_P$42") (pintype "bidirectional"))
    )
    (net (code "231") (name "unconnected-(IC106A-PF1-PadP$43)") (class "Default")
      (node (ref "IC106") (pin "P$43") (pinfunction "PF1_P$43") (pintype "bidirectional"))
    )
    (net (code "232") (name "unconnected-(IC106A-PF4-PadP$46)") (class "Default")
      (node (ref "IC106") (pin "P$46") (pinfunction "PF4_P$46") (pintype "bidirectional"))
    )
    (net (code "233") (name "unconnected-(IC106A-PH2-PadP$31)") (class "Default")
      (node (ref "IC106") (pin "P$31") (pinfunction "PH2_P$31") (pintype "bidirectional"))
    )
    (net (code "234") (name "unconnected-(IC106A-PH3-PadP$32)") (class "Default")
      (node (ref "IC106") (pin "P$32") (pinfunction "PH3_P$32") (pintype "bidirectional"))
    )
    (net (code "235") (name "unconnected-(IC106A-PJ0-PadP$116)") (class "Default")
      (node (ref "IC106") (pin "P$116") (pinfunction "PJ0_P$116") (pintype "bidirectional"))
    )
    (net (code "236") (name "unconnected-(IC106A-PJ1-PadP$117)") (class "Default")
      (node (ref "IC106") (pin "P$117") (pinfunction "PJ1_P$117") (pintype "bidirectional"))
    )
    (net (code "237") (name "unconnected-(IC106A-PK0-PadP$18)") (class "Default")
      (node (ref "IC106") (pin "P$18") (pinfunction "PK0_P$18") (pintype "bidirectional"))
    )
    (net (code "238") (name "unconnected-(IC106A-PK1-PadP$19)") (class "Default")
      (node (ref "IC106") (pin "P$19") (pinfunction "PK1_P$19") (pintype "bidirectional"))
    )
    (net (code "239") (name "unconnected-(IC106A-PK2-PadP$20)") (class "Default")
      (node (ref "IC106") (pin "P$20") (pinfunction "PK2_P$20") (pintype "bidirectional"))
    )
    (net (code "240") (name "unconnected-(IC106A-PK3-PadP$21)") (class "Default")
      (node (ref "IC106") (pin "P$21") (pinfunction "PK3_P$21") (pintype "bidirectional"))
    )
    (net (code "241") (name "unconnected-(IC106A-PK7-PadP$60)") (class "Default")
      (node (ref "IC106") (pin "P$60") (pinfunction "PK7_P$60") (pintype "bidirectional"))
    )
    (net (code "242") (name "unconnected-(IC106A-PM2-PadP$76)") (class "Default")
      (node (ref "IC106") (pin "P$76") (pinfunction "PM2_P$76") (pintype "bidirectional"))
    )
    (net (code "243") (name "unconnected-(IC106A-PM3-PadP$75)") (class "Default")
      (node (ref "IC106") (pin "P$75") (pinfunction "PM3_P$75") (pintype "bidirectional"))
    )
    (net (code "244") (name "unconnected-(IC106A-PM4-PadP$74)") (class "Default")
      (node (ref "IC106") (pin "P$74") (pinfunction "PM4_P$74") (pintype "bidirectional"))
    )
    (net (code "245") (name "unconnected-(IC106A-PM5-PadP$73)") (class "Default")
      (node (ref "IC106") (pin "P$73") (pinfunction "PM5_P$73") (pintype "bidirectional"))
    )
    (net (code "246") (name "unconnected-(IC106A-PM6-PadP$72)") (class "Default")
      (node (ref "IC106") (pin "P$72") (pinfunction "PM6_P$72") (pintype "bidirectional"))
    )
    (net (code "247") (name "unconnected-(IC106A-PM7-PadP$71)") (class "Default")
      (node (ref "IC106") (pin "P$71") (pinfunction "PM7_P$71") (pintype "bidirectional"))
    )
    (net (code "248") (name "unconnected-(IC106A-PN0-PadP$107)") (class "Default")
      (node (ref "IC106") (pin "P$107") (pinfunction "PN0_P$107") (pintype "bidirectional"))
    )
    (net (code "249") (name "unconnected-(IC106A-PN1-PadP$108)") (class "Default")
      (node (ref "IC106") (pin "P$108") (pinfunction "PN1_P$108") (pintype "bidirectional"))
    )
    (net (code "250") (name "unconnected-(IC106A-PN2-PadP$109)") (class "Default")
      (node (ref "IC106") (pin "P$109") (pinfunction "PN2_P$109") (pintype "bidirectional"))
    )
    (net (code "251") (name "unconnected-(IC106A-PN3-PadP$110)") (class "Default")
      (node (ref "IC106") (pin "P$110") (pinfunction "PN3_P$110") (pintype "bidirectional"))
    )
    (net (code "252") (name "unconnected-(IC106A-PN4-PadP$111)") (class "Default")
      (node (ref "IC106") (pin "P$111") (pinfunction "PN4_P$111") (pintype "bidirectional"))
    )
    (net (code "253") (name "unconnected-(IC106A-PN5-PadP$112)") (class "Default")
      (node (ref "IC106") (pin "P$112") (pinfunction "PN5_P$112") (pintype "bidirectional"))
    )
    (net (code "254") (name "unconnected-(IC106A-PP0-PadP$118)") (class "Default")
      (node (ref "IC106") (pin "P$118") (pinfunction "PP0_P$118") (pintype "bidirectional"))
    )
    (net (code "255") (name "unconnected-(IC106A-PP1-PadP$119)") (class "Default")
      (node (ref "IC106") (pin "P$119") (pinfunction "PP1_P$119") (pintype "bidirectional"))
    )
    (net (code "256") (name "unconnected-(IC106A-PQ4-PadP$102)") (class "Default")
      (node (ref "IC106") (pin "P$102") (pinfunction "PQ4_P$102") (pintype "bidirectional"))
    )
    (net (code "257") (name "unconnected-(IC106B-EN0RXIN-PadP$53)") (class "Default")
      (node (ref "IC106") (pin "P$53") (pinfunction "EN0RXIN_P$53") (pintype "bidirectional"))
    )
    (net (code "258") (name "unconnected-(IC106B-EN0RXIP-PadP$54)") (class "Default")
      (node (ref "IC106") (pin "P$54") (pinfunction "EN0RXIP_P$54") (pintype "bidirectional"))
    )
    (net (code "259") (name "unconnected-(IC106B-EN0TXON-PadP$56)") (class "Default")
      (node (ref "IC106") (pin "P$56") (pinfunction "EN0TXON_P$56") (pintype "bidirectional"))
    )
    (net (code "260") (name "unconnected-(IC106B-EN0TXOP-PadP$57)") (class "Default")
      (node (ref "IC106") (pin "P$57") (pinfunction "EN0TXOP_P$57") (pintype "bidirectional"))
    )
    (net (code "261") (name "unconnected-(IC106B-XOSC1-PadP$67)") (class "Default")
      (node (ref "IC106") (pin "P$67") (pinfunction "XOSC1_P$67") (pintype "bidirectional"))
    )
    (net (code "262") (name "unconnected-(IC106B-~{HIB}-PadP$65)") (class "Default")
      (node (ref "IC106") (pin "P$65") (pinfunction "~{HIB}_P$65") (pintype "bidirectional"))
    )
    (net (code "263") (name "unconnected-(IC107-NC-Pad5)") (class "Default")
      (node (ref "IC107") (pin "5") (pinfunction "NC_5") (pintype "passive"))
    )
    (net (code "264") (name "unconnected-(IC107-NC_2-Pad2)") (class "Default")
      (node (ref "IC107") (pin "2") (pinfunction "NC_2_2") (pintype "passive"))
    )
    (net (code "265") (name "unconnected-(IC107-NC_3-Pad4)") (class "Default")
      (node (ref "IC107") (pin "4") (pinfunction "NC_3_4") (pintype "passive"))
    )
    (net (code "266") (name "unconnected-(J101-PadSHIELD1)") (class "Default")
      (node (ref "J101") (pin "SHIELD1") (pinfunction "SHIELD1_SHIELD1") (pintype "bidirectional"))
    )
    (net (code "267") (name "unconnected-(J101-PadSHIELD2)") (class "Default")
      (node (ref "J101") (pin "SHIELD2") (pinfunction "SHIELD2_SHIELD2") (pintype "bidirectional"))
    )
    (net (code "268") (name "unconnected-(J101-PadSHIELD4)") (class "Default")
      (node (ref "J101") (pin "SHIELD4") (pinfunction "SHIELD4_SHIELD4") (pintype "bidirectional"))
    )
    (net (code "269") (name "unconnected-(J101-PadSHIELD5)") (class "Default")
      (node (ref "J101") (pin "SHIELD5") (pinfunction "SHIELD5_SHIELD5") (pintype "bidirectional"))
    )
    (net (code "270") (name "unconnected-(J101-PadSHIELD6)") (class "Default")
      (node (ref "J101") (pin "SHIELD6") (pinfunction "SHIELD6_SHIELD6") (pintype "bidirectional"))
    )
    (net (code "271") (name "unconnected-(Q101-NC-Pad2)") (class "Default")
      (node (ref "Q101") (pin "2") (pinfunction "NC_2") (pintype "bidirectional"))
    )
    (net (code "272") (name "unconnected-(Q101-NC2-Pad4)") (class "Default")
      (node (ref "Q101") (pin "4") (pinfunction "NC2_4") (pintype "bidirectional"))
    )
    (net (code "273") (name "~{RST}") (class "Default")
      (node (ref "C13") (pin "1") (pinfunction "1_1") (pintype "passive"))
      (node (ref "IC111") (pin "7") (pinfunction "3A_7") (pintype "bidirectional"))
      (node (ref "J2") (pin "16") (pinfunction "5_16") (pintype "bidirectional"))
      (node (ref "MSP1") (pin "83") (pinfunction "RSTN/NMI_83") (pintype "power_in"))
      (node (ref "R6") (pin "1") (pinfunction "1_1") (pintype "passive"))
      (node (ref "S3") (pin "2") (pinfunction "S_2") (pintype "passive"))
    )
  )
)
